# schematic.net
KiCad netlist of a schematic drawn in Altium Designer
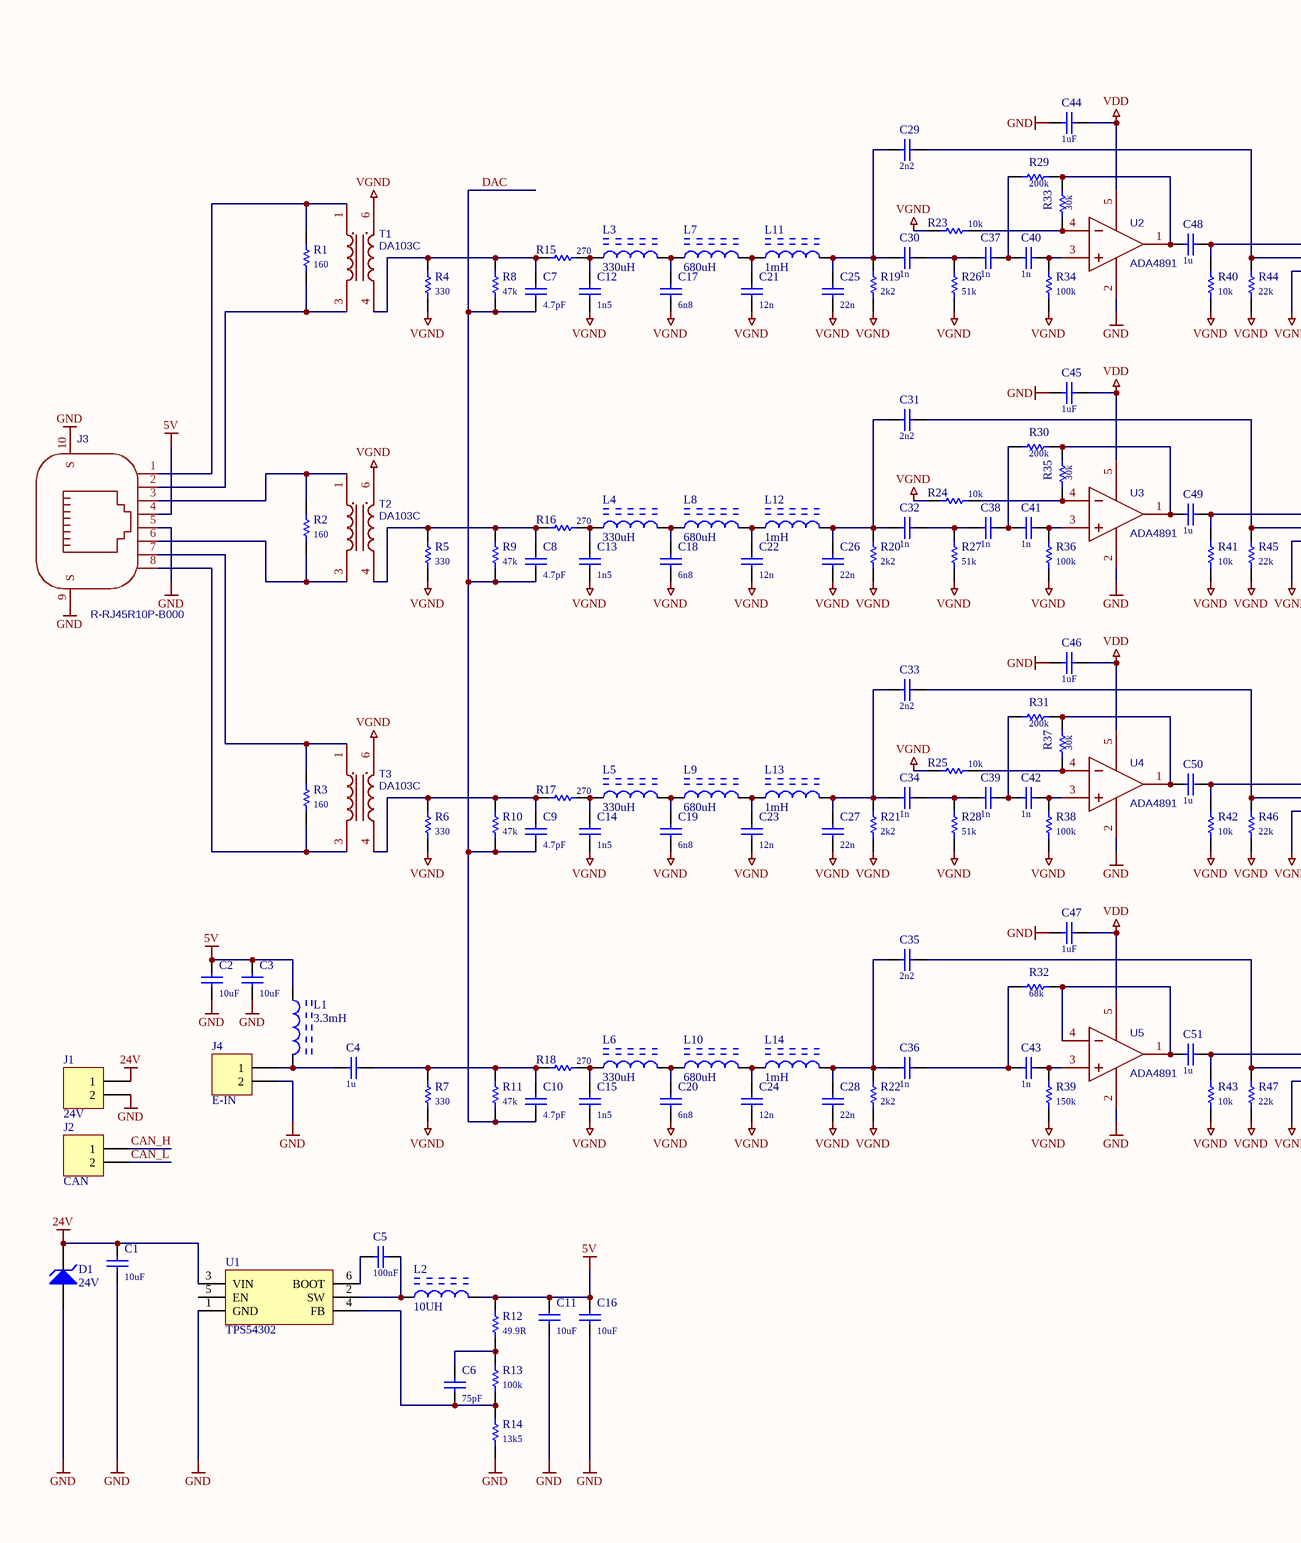
[diagram p0: schematic.SchDoc, left]
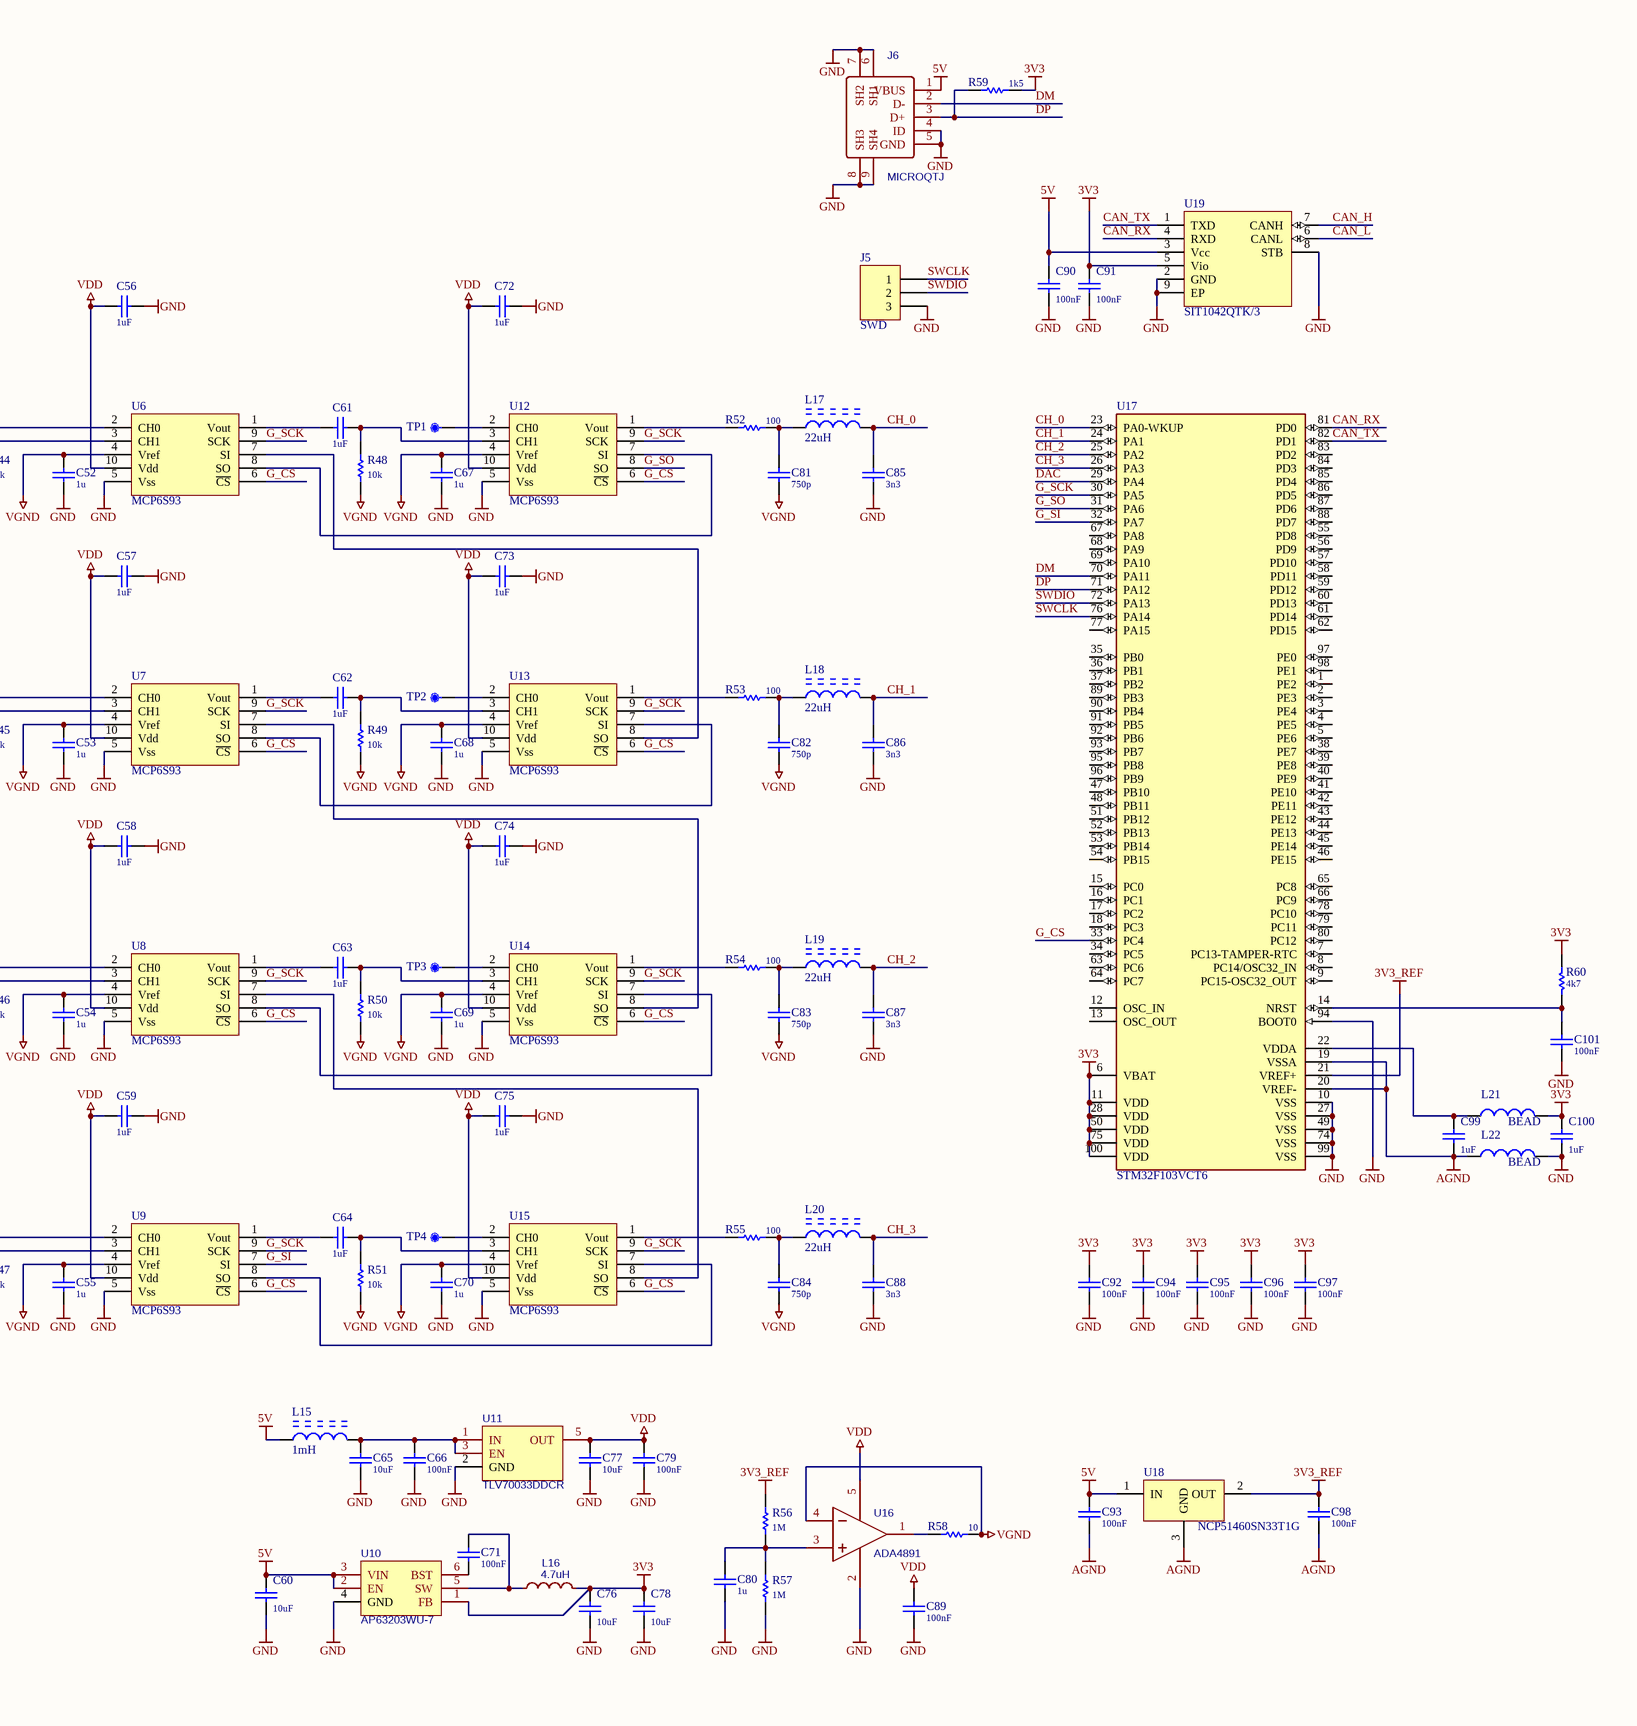
[diagram p1: schematic.SchDoc, right]

(export (version "E")
  (design (tool "Eeschema 10.0.6"))
  (components
    (comp (ref "C1")
      (value "10uF")
      (footprint "C1206")
      (description "10uf 50V 1206")
      (libsource (lib "Miscellaneous Devices") (part "CAP"))
    )
    (comp (ref "C2")
      (value "10uF")
      (footprint "C1206")
      (description "10uf 50V 1206")
      (libsource (lib "Miscellaneous Devices") (part "CAP"))
    )
    (comp (ref "C3")
      (value "10uF")
      (footprint "C1206")
      (description "10uf 50V 1206")
      (libsource (lib "Miscellaneous Devices") (part "CAP"))
    )
    (comp (ref "C4")
      (value "1u")
      (footprint "C0603")
      (description "1u 0603")
      (libsource (lib "Miscellaneous Devices") (part "CAP"))
    )
    (comp (ref "C5")
      (value "100nF")
      (footprint "C0603")
      (description "100nF 0603")
      (libsource (lib "Miscellaneous Devices") (part "CAP"))
    )
    (comp (ref "C6")
      (value "75pF")
      (footprint "C0603")
      (description "75pF 0603")
      (libsource (lib "Miscellaneous Devices") (part "CAP"))
    )
    (comp (ref "C7")
      (value "4.7pF")
      (footprint "C0603")
      (description "4.7pF 0603")
      (libsource (lib "Miscellaneous Devices") (part "CAP"))
    )
    (comp (ref "C8")
      (value "4.7pF")
      (footprint "C0603")
      (description "4.7pF 0603")
      (libsource (lib "Miscellaneous Devices") (part "CAP"))
    )
    (comp (ref "C9")
      (value "4.7pF")
      (footprint "C0603")
      (description "4.7pF 0603")
      (libsource (lib "Miscellaneous Devices") (part "CAP"))
    )
    (comp (ref "C10")
      (value "4.7pF")
      (footprint "C0603")
      (description "4.7pF 0603")
      (libsource (lib "Miscellaneous Devices") (part "CAP"))
    )
    (comp (ref "C11")
      (value "10uF")
      (footprint "C1206")
      (description "10uf 50V 1206")
      (libsource (lib "Miscellaneous Devices") (part "CAP"))
    )
    (comp (ref "C12")
      (value "1n5")
      (footprint "C0603")
      (description "1n5 0603")
      (libsource (lib "Miscellaneous Devices") (part "CAP"))
    )
    (comp (ref "C13")
      (value "1n5")
      (footprint "C0603")
      (description "1n5 0603")
      (libsource (lib "Miscellaneous Devices") (part "CAP"))
    )
    (comp (ref "C14")
      (value "1n5")
      (footprint "C0603")
      (description "1n5 0603")
      (libsource (lib "Miscellaneous Devices") (part "CAP"))
    )
    (comp (ref "C15")
      (value "1n5")
      (footprint "C0603")
      (description "1n5 0603")
      (libsource (lib "Miscellaneous Devices") (part "CAP"))
    )
    (comp (ref "C16")
      (value "10uF")
      (footprint "C1206")
      (description "10uf 50V 1206")
      (libsource (lib "Miscellaneous Devices") (part "CAP"))
    )
    (comp (ref "C17")
      (value "6n8")
      (footprint "C0603")
      (description "6n8 0603")
      (libsource (lib "Miscellaneous Devices") (part "CAP"))
    )
    (comp (ref "C18")
      (value "6n8")
      (footprint "C0603")
      (description "6n8 0603")
      (libsource (lib "Miscellaneous Devices") (part "CAP"))
    )
    (comp (ref "C19")
      (value "6n8")
      (footprint "C0603")
      (description "6n8 0603")
      (libsource (lib "Miscellaneous Devices") (part "CAP"))
    )
    (comp (ref "C20")
      (value "6n8")
      (footprint "C0603")
      (description "6n8 0603")
      (libsource (lib "Miscellaneous Devices") (part "CAP"))
    )
    (comp (ref "C21")
      (value "12n")
      (footprint "C0603")
      (description "12nF 0603")
      (libsource (lib "Miscellaneous Devices") (part "CAP"))
    )
    (comp (ref "C22")
      (value "12n")
      (footprint "C0603")
      (description "12nF 0603")
      (libsource (lib "Miscellaneous Devices") (part "CAP"))
    )
    (comp (ref "C23")
      (value "12n")
      (footprint "C0603")
      (description "12nF 0603")
      (libsource (lib "Miscellaneous Devices") (part "CAP"))
    )
    (comp (ref "C24")
      (value "12n")
      (footprint "C0603")
      (description "12nF 0603")
      (libsource (lib "Miscellaneous Devices") (part "CAP"))
    )
    (comp (ref "C25")
      (value "22n")
      (footprint "C0603")
      (description "22nF 0603")
      (libsource (lib "Miscellaneous Devices") (part "CAP"))
    )
    (comp (ref "C26")
      (value "22n")
      (footprint "C0603")
      (description "22nF 0603")
      (libsource (lib "Miscellaneous Devices") (part "CAP"))
    )
    (comp (ref "C27")
      (value "22n")
      (footprint "C0603")
      (description "22nF 0603")
      (libsource (lib "Miscellaneous Devices") (part "CAP"))
    )
    (comp (ref "C28")
      (value "22n")
      (footprint "C0603")
      (description "22nF 0603")
      (libsource (lib "Miscellaneous Devices") (part "CAP"))
    )
    (comp (ref "C29")
      (value "2n2")
      (footprint "C0603")
      (description "2n2 0603")
      (libsource (lib "Miscellaneous Devices") (part "CAP"))
    )
    (comp (ref "C30")
      (value "1n")
      (footprint "C0603")
      (description "1n 0603")
      (libsource (lib "Miscellaneous Devices") (part "CAP"))
    )
    (comp (ref "C31")
      (value "2n2")
      (footprint "C0603")
      (description "2n2 0603")
      (libsource (lib "Miscellaneous Devices") (part "CAP"))
    )
    (comp (ref "C32")
      (value "1n")
      (footprint "C0603")
      (description "1n 0603")
      (libsource (lib "Miscellaneous Devices") (part "CAP"))
    )
    (comp (ref "C33")
      (value "2n2")
      (footprint "C0603")
      (description "2n2 0603")
      (libsource (lib "Miscellaneous Devices") (part "CAP"))
    )
    (comp (ref "C34")
      (value "1n")
      (footprint "C0603")
      (description "1n 0603")
      (libsource (lib "Miscellaneous Devices") (part "CAP"))
    )
    (comp (ref "C35")
      (value "2n2")
      (footprint "C0603")
      (description "2n2 0603")
      (libsource (lib "Miscellaneous Devices") (part "CAP"))
    )
    (comp (ref "C36")
      (value "1n")
      (footprint "C0603")
      (description "1n 0603")
      (libsource (lib "Miscellaneous Devices") (part "CAP"))
    )
    (comp (ref "C37")
      (value "1n")
      (footprint "C0603")
      (description "1n 0603")
      (libsource (lib "Miscellaneous Devices") (part "CAP"))
    )
    (comp (ref "C38")
      (value "1n")
      (footprint "C0603")
      (description "1n 0603")
      (libsource (lib "Miscellaneous Devices") (part "CAP"))
    )
    (comp (ref "C39")
      (value "1n")
      (footprint "C0603")
      (description "1n 0603")
      (libsource (lib "Miscellaneous Devices") (part "CAP"))
    )
    (comp (ref "C40")
      (value "1n")
      (footprint "C0603")
      (description "1n 0603")
      (libsource (lib "Miscellaneous Devices") (part "CAP"))
    )
    (comp (ref "C41")
      (value "1n")
      (footprint "C0603")
      (description "1n 0603")
      (libsource (lib "Miscellaneous Devices") (part "CAP"))
    )
    (comp (ref "C42")
      (value "1n")
      (footprint "C0603")
      (description "1n 0603")
      (libsource (lib "Miscellaneous Devices") (part "CAP"))
    )
    (comp (ref "C43")
      (value "1n")
      (footprint "C0603")
      (description "1n 0603")
      (libsource (lib "Miscellaneous Devices") (part "CAP"))
    )
    (comp (ref "C44")
      (value "1uF")
      (footprint "C0603")
      (description "1u 0603")
      (libsource (lib "Miscellaneous Devices") (part "CAP"))
    )
    (comp (ref "C45")
      (value "1uF")
      (footprint "C0603")
      (description "1u 0603")
      (libsource (lib "Miscellaneous Devices") (part "CAP"))
    )
    (comp (ref "C46")
      (value "1uF")
      (footprint "C0603")
      (description "1u 0603")
      (libsource (lib "Miscellaneous Devices") (part "CAP"))
    )
    (comp (ref "C47")
      (value "1uF")
      (footprint "C0603")
      (description "1u 0603")
      (libsource (lib "Miscellaneous Devices") (part "CAP"))
    )
    (comp (ref "C48")
      (value "1u")
      (footprint "C0603")
      (description "1u 0603")
      (libsource (lib "Miscellaneous Devices") (part "CAP"))
    )
    (comp (ref "C49")
      (value "1u")
      (footprint "C0603")
      (description "1u 0603")
      (libsource (lib "Miscellaneous Devices") (part "CAP"))
    )
    (comp (ref "C50")
      (value "1u")
      (footprint "C0603")
      (description "1u 0603")
      (libsource (lib "Miscellaneous Devices") (part "CAP"))
    )
    (comp (ref "C51")
      (value "1u")
      (footprint "C0603")
      (description "1u 0603")
      (libsource (lib "Miscellaneous Devices") (part "CAP"))
    )
    (comp (ref "C52")
      (value "1u")
      (footprint "C0603")
      (description "1u 0603")
      (libsource (lib "Miscellaneous Devices") (part "CAP"))
    )
    (comp (ref "C53")
      (value "1u")
      (footprint "C0603")
      (description "1u 0603")
      (libsource (lib "Miscellaneous Devices") (part "CAP"))
    )
    (comp (ref "C54")
      (value "1u")
      (footprint "C0603")
      (description "1u 0603")
      (libsource (lib "Miscellaneous Devices") (part "CAP"))
    )
    (comp (ref "C55")
      (value "1u")
      (footprint "C0603")
      (description "1u 0603")
      (libsource (lib "Miscellaneous Devices") (part "CAP"))
    )
    (comp (ref "C56")
      (value "1uF")
      (footprint "C0603")
      (description "1u 0603")
      (libsource (lib "Miscellaneous Devices") (part "CAP"))
    )
    (comp (ref "C57")
      (value "1uF")
      (footprint "C0603")
      (description "1u 0603")
      (libsource (lib "Miscellaneous Devices") (part "CAP"))
    )
    (comp (ref "C58")
      (value "1uF")
      (footprint "C0603")
      (description "1u 0603")
      (libsource (lib "Miscellaneous Devices") (part "CAP"))
    )
    (comp (ref "C59")
      (value "1uF")
      (footprint "C0603")
      (description "1u 0603")
      (libsource (lib "Miscellaneous Devices") (part "CAP"))
    )
    (comp (ref "C60")
      (value "10uF")
      (footprint "C1206")
      (description "10uf 50V 1206")
      (libsource (lib "Miscellaneous Devices") (part "CAP"))
    )
    (comp (ref "C61")
      (value "1uF")
      (footprint "C0603")
      (description "1u 0603")
      (libsource (lib "Miscellaneous Devices") (part "CAP"))
    )
    (comp (ref "C62")
      (value "1uF")
      (footprint "C0603")
      (description "1u 0603")
      (libsource (lib "Miscellaneous Devices") (part "CAP"))
    )
    (comp (ref "C63")
      (value "1uF")
      (footprint "C0603")
      (description "1u 0603")
      (libsource (lib "Miscellaneous Devices") (part "CAP"))
    )
    (comp (ref "C64")
      (value "1uF")
      (footprint "C0603")
      (description "1u 0603")
      (libsource (lib "Miscellaneous Devices") (part "CAP"))
    )
    (comp (ref "C65")
      (value "10uF")
      (footprint "C0805")
      (description "10uf 50V 1206")
      (libsource (lib "Miscellaneous Devices") (part "CAP"))
    )
    (comp (ref "C66")
      (value "100nF")
      (footprint "C0603")
      (description "100nF 0603")
      (libsource (lib "Miscellaneous Devices") (part "CAP"))
    )
    (comp (ref "C67")
      (value "1u")
      (footprint "C0603")
      (description "1u 0603")
      (libsource (lib "Miscellaneous Devices") (part "CAP"))
    )
    (comp (ref "C68")
      (value "1u")
      (footprint "C0603")
      (description "1u 0603")
      (libsource (lib "Miscellaneous Devices") (part "CAP"))
    )
    (comp (ref "C69")
      (value "1u")
      (footprint "C0603")
      (description "1u 0603")
      (libsource (lib "Miscellaneous Devices") (part "CAP"))
    )
    (comp (ref "C70")
      (value "1u")
      (footprint "C0603")
      (description "1u 0603")
      (libsource (lib "Miscellaneous Devices") (part "CAP"))
    )
    (comp (ref "C71")
      (value "100nF")
      (footprint "C0402")
      (description "100nF 0402")
      (libsource (lib "Miscellaneous Devices") (part "CAP"))
    )
    (comp (ref "C72")
      (value "1uF")
      (footprint "C0603")
      (description "1u 0603")
      (libsource (lib "Miscellaneous Devices") (part "CAP"))
    )
    (comp (ref "C73")
      (value "1uF")
      (footprint "C0603")
      (description "1u 0603")
      (libsource (lib "Miscellaneous Devices") (part "CAP"))
    )
    (comp (ref "C74")
      (value "1uF")
      (footprint "C0603")
      (description "1u 0603")
      (libsource (lib "Miscellaneous Devices") (part "CAP"))
    )
    (comp (ref "C75")
      (value "1uF")
      (footprint "C0603")
      (description "1u 0603")
      (libsource (lib "Miscellaneous Devices") (part "CAP"))
    )
    (comp (ref "C76")
      (value "10uF")
      (footprint "C1206")
      (description "10uf 50V 1206")
      (libsource (lib "Miscellaneous Devices") (part "CAP"))
    )
    (comp (ref "C77")
      (value "10uF")
      (footprint "C0805")
      (description "10uf 50V 1206")
      (libsource (lib "Miscellaneous Devices") (part "CAP"))
    )
    (comp (ref "C78")
      (value "10uF")
      (footprint "C1206")
      (description "10uf 50V 1206")
      (libsource (lib "Miscellaneous Devices") (part "CAP"))
    )
    (comp (ref "C79")
      (value "100nF")
      (footprint "C0603")
      (description "100nF 0603")
      (libsource (lib "Miscellaneous Devices") (part "CAP"))
    )
    (comp (ref "C80")
      (value "1u")
      (footprint "C0603")
      (description "1u 0603")
      (libsource (lib "Miscellaneous Devices") (part "CAP"))
    )
    (comp (ref "C81")
      (value "750p")
      (footprint "C0603")
      (description "750pF 0603")
      (libsource (lib "Miscellaneous Devices") (part "CAP"))
    )
    (comp (ref "C82")
      (value "750p")
      (footprint "C0603")
      (description "750pF 0603")
      (libsource (lib "Miscellaneous Devices") (part "CAP"))
    )
    (comp (ref "C83")
      (value "750p")
      (footprint "C0603")
      (description "750pF 0603")
      (libsource (lib "Miscellaneous Devices") (part "CAP"))
    )
    (comp (ref "C84")
      (value "750p")
      (footprint "C0603")
      (description "750pF 0603")
      (libsource (lib "Miscellaneous Devices") (part "CAP"))
    )
    (comp (ref "C85")
      (value "3n3")
      (footprint "C0603")
      (description "3n3 0603")
      (libsource (lib "Miscellaneous Devices") (part "CAP"))
    )
    (comp (ref "C86")
      (value "3n3")
      (footprint "C0603")
      (description "3n3 0603")
      (libsource (lib "Miscellaneous Devices") (part "CAP"))
    )
    (comp (ref "C87")
      (value "3n3")
      (footprint "C0603")
      (description "3n3 0603")
      (libsource (lib "Miscellaneous Devices") (part "CAP"))
    )
    (comp (ref "C88")
      (value "3n3")
      (footprint "C0603")
      (description "3n3 0603")
      (libsource (lib "Miscellaneous Devices") (part "CAP"))
    )
    (comp (ref "C89")
      (value "100nF")
      (footprint "C0603")
      (description "100nF 0603")
      (libsource (lib "Miscellaneous Devices") (part "CAP"))
    )
    (comp (ref "C90")
      (value "100nF")
      (footprint "C0402")
      (description "100nF 0402")
      (libsource (lib "Miscellaneous Devices") (part "CAP"))
    )
    (comp (ref "C91")
      (value "100nF")
      (footprint "C0402")
      (description "100nF 0402")
      (libsource (lib "Miscellaneous Devices") (part "CAP"))
    )
    (comp (ref "C92")
      (value "100nF")
      (footprint "C0402")
      (description "100nF 0402")
      (libsource (lib "Miscellaneous Devices") (part "CAP"))
    )
    (comp (ref "C93")
      (value "100nF")
      (footprint "C0603")
      (description "100nF 0603")
      (libsource (lib "Miscellaneous Devices") (part "CAP"))
    )
    (comp (ref "C94")
      (value "100nF")
      (footprint "C0402")
      (description "100nF 0402")
      (libsource (lib "Miscellaneous Devices") (part "CAP"))
    )
    (comp (ref "C95")
      (value "100nF")
      (footprint "C0402")
      (description "100nF 0402")
      (libsource (lib "Miscellaneous Devices") (part "CAP"))
    )
    (comp (ref "C96")
      (value "100nF")
      (footprint "C0402")
      (description "100nF 0402")
      (libsource (lib "Miscellaneous Devices") (part "CAP"))
    )
    (comp (ref "C97")
      (value "100nF")
      (footprint "C0402")
      (description "100nF 0402")
      (libsource (lib "Miscellaneous Devices") (part "CAP"))
    )
    (comp (ref "C98")
      (value "100nF")
      (footprint "C0603")
      (description "100nF 0603")
      (libsource (lib "Miscellaneous Devices") (part "CAP"))
    )
    (comp (ref "C99")
      (value "1uF")
      (footprint "C0603")
      (description "1u 0603")
      (libsource (lib "Miscellaneous Devices") (part "CAP"))
    )
    (comp (ref "C100")
      (value "1uF")
      (footprint "C0603")
      (description "1u 0603")
      (libsource (lib "Miscellaneous Devices") (part "CAP"))
    )
    (comp (ref "C101")
      (value "100nF")
      (footprint "C0402")
      (description "100nF 0402")
      (libsource (lib "Miscellaneous Devices") (part "CAP"))
    )
    (comp (ref "D1")
      (value "24V")
      (footprint "SMB")
      (description "P6SMB24A")
      (libsource (lib "Miscellaneous Devices") (part "SMCJ54A"))
    )
    (comp (ref "J1")
      (value "24V")
      (footprint "CONN_DG308-2.54-2P")
      (description "DG308-2.54-02P-14-00A(H)")
      (libsource (lib "Miscellaneous Devices") (part "CONN MOLEX HDR-M 1x4"))
    )
    (comp (ref "J2")
      (value "CAN")
      (footprint "CONN_DG308-2.54-2P")
      (description "DG308-2.54-02P-14-00A(H)")
      (libsource (lib "Miscellaneous Devices") (part "CONN MOLEX HDR-M 1x4"))
    )
    (comp (ref "J3")
      (value "R-RJ45R10P-B000")
      (footprint "RJ45-TH_R-RJ45R10P-B000")
      (libsource (lib "altium-import") (part "root_3_mirrored_R-RJ45R10P-B000_"))
    )
    (comp (ref "J4")
      (value "E-IN")
      (footprint "CONN_F_TYPE")
      (libsource (lib "Miscellaneous Devices") (part "CONN MOLEX HDR-M 1x4"))
    )
    (comp (ref "J5")
      (value "SWD")
      (footprint "HDR-1X3")
      (libsource (lib "Miscellaneous Devices") (part "Header 3"))
    )
    (comp (ref "J6")
      (value "MICROQTJ")
      (footprint "MICRO-USB-SMD_MICROQTJ")
      (description "MicroQTJ")
      (libsource (lib "altium-import") (part "root_0_MICROQTJ_"))
    )
    (comp (ref "L1")
      (value "3.3mH")
      (footprint "IND-TH_BD5.0-L10.5-P14.50-D0.6")
      (description "CKL0510*3.3mH/K-A T")
      (libsource (lib "Miscellaneous Devices") (part "SRN3015-4R7M"))
    )
    (comp (ref "L2")
      (value "10UH")
      (footprint "IND-SMD_L7.2-W6.6_GPSR07X0")
      (description "CYA0630-10UH")
      (libsource (lib "Miscellaneous Devices") (part "SRN3015-100M"))
    )
    (comp (ref "L3")
      (value "330uH")
      (footprint "L1210")
      (description "NLCV32T-331K-PF")
      (libsource (lib "Miscellaneous Devices") (part "SRN3015-4R7M"))
    )
    (comp (ref "L4")
      (value "330uH")
      (footprint "L1210")
      (description "NLCV32T-331K-PF")
      (libsource (lib "Miscellaneous Devices") (part "SRN3015-4R7M"))
    )
    (comp (ref "L5")
      (value "330uH")
      (footprint "L1210")
      (description "NLCV32T-331K-PF")
      (libsource (lib "Miscellaneous Devices") (part "SRN3015-4R7M"))
    )
    (comp (ref "L6")
      (value "330uH")
      (footprint "L1210")
      (description "NLCV32T-331K-PF")
      (libsource (lib "Miscellaneous Devices") (part "SRN3015-4R7M"))
    )
    (comp (ref "L7")
      (value "680uH")
      (footprint "L1210")
      (description "LQH32CN561K23L")
      (libsource (lib "Miscellaneous Devices") (part "SRN3015-4R7M"))
    )
    (comp (ref "L8")
      (value "680uH")
      (footprint "L1210")
      (description "LQH32CN561K23L")
      (libsource (lib "Miscellaneous Devices") (part "SRN3015-4R7M"))
    )
    (comp (ref "L9")
      (value "680uH")
      (footprint "L1210")
      (description "LQH32CN561K23L")
      (libsource (lib "Miscellaneous Devices") (part "SRN3015-4R7M"))
    )
    (comp (ref "L10")
      (value "680uH")
      (footprint "L1210")
      (description "LQH32CN561K23L")
      (libsource (lib "Miscellaneous Devices") (part "SRN3015-4R7M"))
    )
    (comp (ref "L11")
      (value "1mH")
      (footprint "L1210")
      (description "NLFV32T-102K-EF")
      (libsource (lib "Miscellaneous Devices") (part "SRN3015-4R7M"))
    )
    (comp (ref "L12")
      (value "1mH")
      (footprint "L1210")
      (description "NLFV32T-102K-EF")
      (libsource (lib "Miscellaneous Devices") (part "SRN3015-4R7M"))
    )
    (comp (ref "L13")
      (value "1mH")
      (footprint "L1210")
      (description "NLFV32T-102K-EF")
      (libsource (lib "Miscellaneous Devices") (part "SRN3015-4R7M"))
    )
    (comp (ref "L14")
      (value "1mH")
      (footprint "L1210")
      (description "NLFV32T-102K-EF")
      (libsource (lib "Miscellaneous Devices") (part "SRN3015-4R7M"))
    )
    (comp (ref "L15")
      (value "1mH")
      (footprint "L1210")
      (description "NLFV32T-102K-EF")
      (libsource (lib "Miscellaneous Devices") (part "SRN3015-4R7M"))
    )
    (comp (ref "L16")
      (value "4.7uH")
      (footprint "IND-SMD_L4.4-W4.2")
      (description "FXL0420-4R7-M")
      (libsource (lib "altium-import") (part "root_0_4.7uH_"))
    )
    (comp (ref "L17")
      (value "22uH")
      (footprint "L1210")
      (description "NLCV32T-220K-PF")
      (libsource (lib "Miscellaneous Devices") (part "SRN3015-4R7M"))
    )
    (comp (ref "L18")
      (value "22uH")
      (footprint "L1210")
      (description "NLCV32T-220K-PF")
      (libsource (lib "Miscellaneous Devices") (part "SRN3015-4R7M"))
    )
    (comp (ref "L19")
      (value "22uH")
      (footprint "L1210")
      (description "NLCV32T-220K-PF")
      (libsource (lib "Miscellaneous Devices") (part "SRN3015-4R7M"))
    )
    (comp (ref "L20")
      (value "22uH")
      (footprint "L1210")
      (description "NLCV32T-220K-PF")
      (libsource (lib "Miscellaneous Devices") (part "SRN3015-4R7M"))
    )
    (comp (ref "L21")
      (value "BEAD")
      (footprint "L0402")
      (description "BEAD 0402")
      (libsource (lib "Miscellaneous Devices") (part "BLM18AG601SN1D"))
    )
    (comp (ref "L22")
      (value "BEAD")
      (footprint "L0402")
      (description "BEAD 0402")
      (libsource (lib "Miscellaneous Devices") (part "BLM18AG601SN1D"))
    )
    (comp (ref "R1")
      (value "160")
      (footprint "R0603")
      (description "160R 0603")
      (libsource (lib "Miscellaneous Devices") (part "RES"))
    )
    (comp (ref "R2")
      (value "160")
      (footprint "R0603")
      (description "160R 0603")
      (libsource (lib "Miscellaneous Devices") (part "RES"))
    )
    (comp (ref "R3")
      (value "160")
      (footprint "R0603")
      (description "160R 0603")
      (libsource (lib "Miscellaneous Devices") (part "RES"))
    )
    (comp (ref "R4")
      (value "330")
      (footprint "R0603")
      (description "330R 0603")
      (libsource (lib "Miscellaneous Devices") (part "RES"))
    )
    (comp (ref "R5")
      (value "330")
      (footprint "R0603")
      (description "330R 0603")
      (libsource (lib "Miscellaneous Devices") (part "RES"))
    )
    (comp (ref "R6")
      (value "330")
      (footprint "R0603")
      (description "330R 0603")
      (libsource (lib "Miscellaneous Devices") (part "RES"))
    )
    (comp (ref "R7")
      (value "330")
      (footprint "R0603")
      (description "330R 0603")
      (libsource (lib "Miscellaneous Devices") (part "RES"))
    )
    (comp (ref "R8")
      (value "47k")
      (footprint "R0603")
      (description "47k 0603")
      (libsource (lib "Miscellaneous Devices") (part "RES"))
    )
    (comp (ref "R9")
      (value "47k")
      (footprint "R0603")
      (description "47k 0603")
      (libsource (lib "Miscellaneous Devices") (part "RES"))
    )
    (comp (ref "R10")
      (value "47k")
      (footprint "R0603")
      (description "47k 0603")
      (libsource (lib "Miscellaneous Devices") (part "RES"))
    )
    (comp (ref "R11")
      (value "47k")
      (footprint "R0603")
      (description "47k 0603")
      (libsource (lib "Miscellaneous Devices") (part "RES"))
    )
    (comp (ref "R12")
      (value "49.9R")
      (footprint "R0603")
      (description "49R9 0603")
      (libsource (lib "Miscellaneous Devices") (part "RES"))
    )
    (comp (ref "R13")
      (value "100k")
      (footprint "R0603")
      (description "100k 0603")
      (libsource (lib "") (part "RES_1"))
    )
    (comp (ref "R14")
      (value "13k5")
      (footprint "R0603")
      (description "13k7 0603")
      (libsource (lib "") (part "RES_1"))
    )
    (comp (ref "R15")
      (value "270")
      (footprint "R0603")
      (description "270R 0603")
      (libsource (lib "Miscellaneous Devices") (part "RES"))
    )
    (comp (ref "R16")
      (value "270")
      (footprint "R0603")
      (description "270R 0603")
      (libsource (lib "Miscellaneous Devices") (part "RES"))
    )
    (comp (ref "R17")
      (value "270")
      (footprint "R0603")
      (description "270R 0603")
      (libsource (lib "Miscellaneous Devices") (part "RES"))
    )
    (comp (ref "R18")
      (value "270")
      (footprint "R0603")
      (description "270R 0603")
      (libsource (lib "Miscellaneous Devices") (part "RES"))
    )
    (comp (ref "R19")
      (value "2k2")
      (footprint "R0603")
      (description "2k2 0603")
      (libsource (lib "Miscellaneous Devices") (part "RES"))
    )
    (comp (ref "R20")
      (value "2k2")
      (footprint "R0603")
      (description "2k2 0603")
      (libsource (lib "Miscellaneous Devices") (part "RES"))
    )
    (comp (ref "R21")
      (value "2k2")
      (footprint "R0603")
      (description "2k2 0603")
      (libsource (lib "Miscellaneous Devices") (part "RES"))
    )
    (comp (ref "R22")
      (value "2k2")
      (footprint "R0603")
      (description "2k2 0603")
      (libsource (lib "Miscellaneous Devices") (part "RES"))
    )
    (comp (ref "R23")
      (value "10k")
      (footprint "R0603")
      (description "10k 0603")
      (libsource (lib "Miscellaneous Devices") (part "RES"))
    )
    (comp (ref "R24")
      (value "10k")
      (footprint "R0603")
      (description "10k 0603")
      (libsource (lib "Miscellaneous Devices") (part "RES"))
    )
    (comp (ref "R25")
      (value "10k")
      (footprint "R0603")
      (description "10k 0603")
      (libsource (lib "Miscellaneous Devices") (part "RES"))
    )
    (comp (ref "R26")
      (value "51k")
      (footprint "R0603")
      (description "51k 0603")
      (libsource (lib "Miscellaneous Devices") (part "RES"))
    )
    (comp (ref "R27")
      (value "51k")
      (footprint "R0603")
      (description "51k 0603")
      (libsource (lib "Miscellaneous Devices") (part "RES"))
    )
    (comp (ref "R28")
      (value "51k")
      (footprint "R0603")
      (description "51k 0603")
      (libsource (lib "Miscellaneous Devices") (part "RES"))
    )
    (comp (ref "R29")
      (value "200k")
      (footprint "R0603")
      (description "200k 0603")
      (libsource (lib "Miscellaneous Devices") (part "RES"))
    )
    (comp (ref "R30")
      (value "200k")
      (footprint "R0603")
      (description "200k 0603")
      (libsource (lib "Miscellaneous Devices") (part "RES"))
    )
    (comp (ref "R31")
      (value "200k")
      (footprint "R0603")
      (description "200k 0603")
      (libsource (lib "Miscellaneous Devices") (part "RES"))
    )
    (comp (ref "R32")
      (value "68k")
      (footprint "R0603")
      (description "68k 0603")
      (libsource (lib "Miscellaneous Devices") (part "RES"))
    )
    (comp (ref "R33")
      (value "30k")
      (footprint "R0603")
      (description "30k 0603")
      (libsource (lib "Miscellaneous Devices") (part "RES"))
    )
    (comp (ref "R34")
      (value "100k")
      (footprint "R0603")
      (description "100k 0603")
      (libsource (lib "Miscellaneous Devices") (part "RES"))
    )
    (comp (ref "R35")
      (value "30k")
      (footprint "R0603")
      (description "30k 0603")
      (libsource (lib "Miscellaneous Devices") (part "RES"))
    )
    (comp (ref "R36")
      (value "100k")
      (footprint "R0603")
      (description "100k 0603")
      (libsource (lib "Miscellaneous Devices") (part "RES"))
    )
    (comp (ref "R37")
      (value "30k")
      (footprint "R0603")
      (description "30k 0603")
      (libsource (lib "Miscellaneous Devices") (part "RES"))
    )
    (comp (ref "R38")
      (value "100k")
      (footprint "R0603")
      (description "100k 0603")
      (libsource (lib "Miscellaneous Devices") (part "RES"))
    )
    (comp (ref "R39")
      (value "150k")
      (footprint "R0603")
      (description "150k 0603")
      (libsource (lib "Miscellaneous Devices") (part "RES"))
    )
    (comp (ref "R40")
      (value "10k")
      (footprint "R0603")
      (description "10k 0603")
      (libsource (lib "Miscellaneous Devices") (part "RES"))
    )
    (comp (ref "R41")
      (value "10k")
      (footprint "R0603")
      (description "10k 0603")
      (libsource (lib "Miscellaneous Devices") (part "RES"))
    )
    (comp (ref "R42")
      (value "10k")
      (footprint "R0603")
      (description "10k 0603")
      (libsource (lib "Miscellaneous Devices") (part "RES"))
    )
    (comp (ref "R43")
      (value "10k")
      (footprint "R0603")
      (description "10k 0603")
      (libsource (lib "Miscellaneous Devices") (part "RES"))
    )
    (comp (ref "R44")
      (value "22k")
      (footprint "R0603")
      (description "22k 0603")
      (libsource (lib "Miscellaneous Devices") (part "RES"))
    )
    (comp (ref "R45")
      (value "22k")
      (footprint "R0603")
      (description "22k 0603")
      (libsource (lib "Miscellaneous Devices") (part "RES"))
    )
    (comp (ref "R46")
      (value "22k")
      (footprint "R0603")
      (description "22k 0603")
      (libsource (lib "Miscellaneous Devices") (part "RES"))
    )
    (comp (ref "R47")
      (value "22k")
      (footprint "R0603")
      (description "22k 0603")
      (libsource (lib "Miscellaneous Devices") (part "RES"))
    )
    (comp (ref "R48")
      (value "10k")
      (footprint "R0603")
      (description "10k 0603")
      (libsource (lib "Miscellaneous Devices") (part "RES"))
    )
    (comp (ref "R49")
      (value "10k")
      (footprint "R0603")
      (description "10k 0603")
      (libsource (lib "Miscellaneous Devices") (part "RES"))
    )
    (comp (ref "R50")
      (value "10k")
      (footprint "R0603")
      (description "10k 0603")
      (libsource (lib "Miscellaneous Devices") (part "RES"))
    )
    (comp (ref "R51")
      (value "10k")
      (footprint "R0603")
      (description "10k 0603")
      (libsource (lib "Miscellaneous Devices") (part "RES"))
    )
    (comp (ref "R52")
      (value "100")
      (footprint "R0603")
      (description "100R 0603")
      (libsource (lib "Miscellaneous Devices") (part "RES"))
    )
    (comp (ref "R53")
      (value "100")
      (footprint "R0603")
      (description "100R 0603")
      (libsource (lib "Miscellaneous Devices") (part "RES"))
    )
    (comp (ref "R54")
      (value "100")
      (footprint "R0603")
      (description "100R 0603")
      (libsource (lib "Miscellaneous Devices") (part "RES"))
    )
    (comp (ref "R55")
      (value "100")
      (footprint "R0603")
      (description "100R 0603")
      (libsource (lib "Miscellaneous Devices") (part "RES"))
    )
    (comp (ref "R56")
      (value "1M")
      (footprint "R0603")
      (description "1M 0603")
      (libsource (lib "Miscellaneous Devices") (part "RES"))
    )
    (comp (ref "R57")
      (value "1M")
      (footprint "R0603")
      (description "1M 0603")
      (libsource (lib "Miscellaneous Devices") (part "RES"))
    )
    (comp (ref "R58")
      (value "10")
      (footprint "R0805")
      (description "10R 0805")
      (libsource (lib "Miscellaneous Devices") (part "RES"))
    )
    (comp (ref "R59")
      (value "1k5")
      (footprint "R0402")
      (description "1k5 0402")
      (libsource (lib "Miscellaneous Devices") (part "RES"))
    )
    (comp (ref "R60")
      (value "4k7")
      (footprint "R0402")
      (description "4k7 0402")
      (libsource (lib "") (part "RES_1"))
    )
    (comp (ref "T1")
      (value "DA103C")
      (footprint "TR_DA103C")
      (libsource (lib "altium-import") (part "root_3_mirrored_DLW43SH101XK2L_"))
    )
    (comp (ref "T2")
      (value "DA103C")
      (footprint "TR_DA103C")
      (libsource (lib "altium-import") (part "root_3_mirrored_DLW43SH101XK2L_"))
    )
    (comp (ref "T3")
      (value "DA103C")
      (footprint "TR_DA103C")
      (libsource (lib "altium-import") (part "root_3_mirrored_DLW43SH101XK2L_"))
    )
    (comp (ref "TP1")
      (value "~")
      (footprint "TP_TH_MICRO")
      (libsource (lib "Miscellaneous Devices") (part "TP_Dup1"))
    )
    (comp (ref "TP2")
      (value "~")
      (footprint "TP_TH_MICRO")
      (libsource (lib "Miscellaneous Devices") (part "TP_Dup1"))
    )
    (comp (ref "TP3")
      (value "~")
      (footprint "TP_TH_MICRO")
      (libsource (lib "Miscellaneous Devices") (part "TP_Dup1"))
    )
    (comp (ref "TP4")
      (value "~")
      (footprint "TP_TH_MICRO")
      (libsource (lib "Miscellaneous Devices") (part "TP_Dup1"))
    )
    (comp (ref "U1")
      (value "TPS54302")
      (footprint "SOT-23-6")
      (description "TPS54302DDCR")
      (libsource (lib "Miscellaneous Devices") (part "LM27313XMFX"))
    )
    (comp (ref "U2")
      (value "ADA4891")
      (footprint "SOT-23-5")
      (description "ADA4891-1ARJZ-R7")
      (libsource (lib "altium-import") (part "root_0_ADA4891-1ARJZ-R7_"))
    )
    (comp (ref "U3")
      (value "ADA4891")
      (footprint "SOT-23-5")
      (description "ADA4891-1ARJZ-R7")
      (libsource (lib "altium-import") (part "root_0_ADA4891-1ARJZ-R7_"))
    )
    (comp (ref "U4")
      (value "ADA4891")
      (footprint "SOT-23-5")
      (description "ADA4891-1ARJZ-R7")
      (libsource (lib "altium-import") (part "root_0_ADA4891-1ARJZ-R7_"))
    )
    (comp (ref "U5")
      (value "ADA4891")
      (footprint "SOT-23-5")
      (description "ADA4891-1ARJZ-R7")
      (libsource (lib "altium-import") (part "root_0_ADA4891-1ARJZ-R7_"))
    )
    (comp (ref "U6") (value "MCP6S93") (footprint "MSOP10") (libsource (lib "Schlib1") (part "MCP6S93")))
    (comp (ref "U7") (value "MCP6S93") (footprint "MSOP10") (libsource (lib "Schlib1") (part "MCP6S93")))
    (comp (ref "U8") (value "MCP6S93") (footprint "MSOP10") (libsource (lib "Schlib1") (part "MCP6S93")))
    (comp (ref "U9") (value "MCP6S93") (footprint "MSOP10") (libsource (lib "Schlib1") (part "MCP6S93")))
    (comp (ref "U10")
      (value "AP63203WU-7")
      (footprint "SOT-23-6")
      (libsource (lib "Schlib1") (part "AP63203WU-7"))
    )
    (comp (ref "U11")
      (value "TLV70033DDCR")
      (footprint "SOT-23-5")
      (libsource (lib "Schlib1") (part "TLV70033DDCR"))
    )
    (comp (ref "U12") (value "MCP6S93") (footprint "MSOP10") (libsource (lib "Schlib1") (part "MCP6S93")))
    (comp (ref "U13") (value "MCP6S93") (footprint "MSOP10") (libsource (lib "Schlib1") (part "MCP6S93")))
    (comp (ref "U14") (value "MCP6S93") (footprint "MSOP10") (libsource (lib "Schlib1") (part "MCP6S93")))
    (comp (ref "U15") (value "MCP6S93") (footprint "MSOP10") (libsource (lib "Schlib1") (part "MCP6S93")))
    (comp (ref "U16")
      (value "ADA4891")
      (footprint "SOT-23-5")
      (description "ADA4891-1ARJZ-R7")
      (libsource (lib "altium-import") (part "root_0_ADA4891-1ARJZ-R7_"))
    )
    (comp (ref "U17")
      (value "STM32F103VCT6")
      (footprint "lib_2023:LQFP-100")
      (libsource (lib "SnapEDAsch") (part "STM32F103VCT6"))
    )
    (comp (ref "U18")
      (value "NCP51460SN33T1G")
      (footprint "SOT-23")
      (libsource (lib "Schlib1") (part "NCP51460SN33T1G"))
    )
    (comp (ref "U19")
      (value "SIT1042QTK/3")
      (footprint "DFN8_3X3_P065")
      (libsource (lib "Miscellaneous Devices") (part "LTC2875"))
    )
  )
  (nets
    (net (code "1") (name "/CAN_H") (class "Default")
      (node (ref "J2") (pin "1") (pinfunction "1_1") (pintype "passive"))
      (node (ref "U19") (pin "7") (pinfunction "CANH_7") (pintype "bidirectional"))
    )
    (net (code "2") (name "/CAN_L") (class "Default")
      (node (ref "J2") (pin "2") (pinfunction "2_2") (pintype "passive"))
      (node (ref "U19") (pin "6") (pinfunction "CANL_6") (pintype "bidirectional"))
    )
    (net (code "3") (name "/CAN_RX") (class "Default")
      (node (ref "U17") (pin "81") (pinfunction "PD0_81") (pintype "bidirectional"))
      (node (ref "U19") (pin "4") (pinfunction "RXD_4") (pintype "passive"))
    )
    (net (code "4") (name "/CAN_TX") (class "Default")
      (node (ref "U17") (pin "82") (pinfunction "PD1_82") (pintype "bidirectional"))
      (node (ref "U19") (pin "1") (pinfunction "TXD_1") (pintype "passive"))
    )
    (net (code "5") (name "/CH_0") (class "Default")
      (node (ref "C85") (pin "1") (pinfunction "1_1") (pintype "passive"))
      (node (ref "L17") (pin "2") (pinfunction "2_2") (pintype "passive"))
      (node (ref "U17") (pin "23") (pinfunction "PA0-WKUP_23") (pintype "bidirectional"))
    )
    (net (code "6") (name "/CH_1") (class "Default")
      (node (ref "C86") (pin "1") (pinfunction "1_1") (pintype "passive"))
      (node (ref "L18") (pin "2") (pinfunction "2_2") (pintype "passive"))
      (node (ref "U17") (pin "24") (pinfunction "PA1_24") (pintype "bidirectional"))
    )
    (net (code "7") (name "/CH_2") (class "Default")
      (node (ref "C87") (pin "1") (pinfunction "1_1") (pintype "passive"))
      (node (ref "L19") (pin "2") (pinfunction "2_2") (pintype "passive"))
      (node (ref "U17") (pin "25") (pinfunction "PA2_25") (pintype "bidirectional"))
    )
    (net (code "8") (name "/CH_3") (class "Default")
      (node (ref "C88") (pin "1") (pinfunction "1_1") (pintype "passive"))
      (node (ref "L20") (pin "2") (pinfunction "2_2") (pintype "passive"))
      (node (ref "U17") (pin "26") (pinfunction "PA3_26") (pintype "bidirectional"))
    )
    (net (code "9") (name "/DAC") (class "Default")
      (node (ref "C10") (pin "1") (pinfunction "1_1") (pintype "passive"))
      (node (ref "C7") (pin "1") (pinfunction "1_1") (pintype "passive"))
      (node (ref "C8") (pin "1") (pinfunction "1_1") (pintype "passive"))
      (node (ref "C9") (pin "1") (pinfunction "1_1") (pintype "passive"))
      (node (ref "R10") (pin "1") (pinfunction "1_1") (pintype "passive"))
      (node (ref "R11") (pin "1") (pinfunction "1_1") (pintype "passive"))
      (node (ref "R8") (pin "1") (pinfunction "1_1") (pintype "passive"))
      (node (ref "R9") (pin "1") (pinfunction "1_1") (pintype "passive"))
      (node (ref "U17") (pin "29") (pinfunction "PA4_29") (pintype "bidirectional"))
    )
    (net (code "10") (name "/DM") (class "Default")
      (node (ref "J6") (pin "2") (pinfunction "D-_2") (pintype "passive"))
      (node (ref "U17") (pin "70") (pinfunction "PA11_70") (pintype "bidirectional"))
    )
    (net (code "11") (name "/DP") (class "Default")
      (node (ref "J6") (pin "3") (pinfunction "D+_3") (pintype "passive"))
      (node (ref "R59") (pin "2") (pinfunction "2_2") (pintype "passive"))
      (node (ref "U17") (pin "71") (pinfunction "PA12_71") (pintype "bidirectional"))
    )
    (net (code "12") (name "/G_CS") (class "Default")
      (node (ref "U12") (pin "6") (pinfunction "~{CS}_6") (pintype "passive"))
      (node (ref "U13") (pin "6") (pinfunction "~{CS}_6") (pintype "passive"))
      (node (ref "U14") (pin "6") (pinfunction "~{CS}_6") (pintype "passive"))
      (node (ref "U15") (pin "6") (pinfunction "~{CS}_6") (pintype "passive"))
      (node (ref "U17") (pin "33") (pinfunction "PC4_33") (pintype "bidirectional"))
      (node (ref "U6") (pin "6") (pinfunction "~{CS}_6") (pintype "passive"))
      (node (ref "U7") (pin "6") (pinfunction "~{CS}_6") (pintype "passive"))
      (node (ref "U8") (pin "6") (pinfunction "~{CS}_6") (pintype "passive"))
      (node (ref "U9") (pin "6") (pinfunction "~{CS}_6") (pintype "passive"))
    )
    (net (code "13") (name "/G_SCK") (class "Default")
      (node (ref "U12") (pin "9") (pinfunction "SCK_9") (pintype "passive"))
      (node (ref "U13") (pin "9") (pinfunction "SCK_9") (pintype "passive"))
      (node (ref "U14") (pin "9") (pinfunction "SCK_9") (pintype "passive"))
      (node (ref "U15") (pin "9") (pinfunction "SCK_9") (pintype "passive"))
      (node (ref "U17") (pin "30") (pinfunction "PA5_30") (pintype "bidirectional"))
      (node (ref "U6") (pin "9") (pinfunction "SCK_9") (pintype "passive"))
      (node (ref "U7") (pin "9") (pinfunction "SCK_9") (pintype "passive"))
      (node (ref "U8") (pin "9") (pinfunction "SCK_9") (pintype "passive"))
      (node (ref "U9") (pin "9") (pinfunction "SCK_9") (pintype "passive"))
    )
    (net (code "14") (name "/G_SI") (class "Default")
      (node (ref "U17") (pin "32") (pinfunction "PA7_32") (pintype "bidirectional"))
      (node (ref "U9") (pin "7") (pinfunction "SI_7") (pintype "passive"))
    )
    (net (code "15") (name "/G_SO") (class "Default")
      (node (ref "U12") (pin "8") (pinfunction "SO_8") (pintype "passive"))
      (node (ref "U17") (pin "31") (pinfunction "PA6_31") (pintype "bidirectional"))
    )
    (net (code "16") (name "/SWCLK") (class "Default")
      (node (ref "J5") (pin "1") (pinfunction "1_1") (pintype "passive"))
      (node (ref "U17") (pin "76") (pinfunction "PA14_76") (pintype "bidirectional"))
    )
    (net (code "17") (name "/SWDIO") (class "Default")
      (node (ref "J5") (pin "2") (pinfunction "2_2") (pintype "passive"))
      (node (ref "U17") (pin "72") (pinfunction "PA13_72") (pintype "bidirectional"))
    )
    (net (code "18") (name "3V3") (class "Default")
      (node (ref "C100") (pin "2") (pinfunction "2_2") (pintype "passive"))
      (node (ref "C76") (pin "2") (pinfunction "2_2") (pintype "passive"))
      (node (ref "C78") (pin "2") (pinfunction "2_2") (pintype "passive"))
      (node (ref "C91") (pin "2") (pinfunction "2_2") (pintype "passive"))
      (node (ref "C92") (pin "2") (pinfunction "2_2") (pintype "passive"))
      (node (ref "C94") (pin "2") (pinfunction "2_2") (pintype "passive"))
      (node (ref "C95") (pin "2") (pinfunction "2_2") (pintype "passive"))
      (node (ref "C96") (pin "2") (pinfunction "2_2") (pintype "passive"))
      (node (ref "C97") (pin "2") (pinfunction "2_2") (pintype "passive"))
      (node (ref "L16") (pin "2") (pinfunction "2_2") (pintype "passive"))
      (node (ref "L21") (pin "1") (pinfunction "1_1") (pintype "passive"))
      (node (ref "R59") (pin "1") (pinfunction "1_1") (pintype "passive"))
      (node (ref "R60") (pin "1") (pinfunction "1_1") (pintype "passive"))
      (node (ref "U10") (pin "1") (pinfunction "FB_1") (pintype "passive"))
      (node (ref "U17") (pin "100") (pinfunction "VDD_100") (pintype "power_in"))
      (node (ref "U17") (pin "11") (pinfunction "VDD_11") (pintype "power_in"))
      (node (ref "U17") (pin "28") (pinfunction "VDD_28") (pintype "power_in"))
      (node (ref "U17") (pin "50") (pinfunction "VDD_50") (pintype "power_in"))
      (node (ref "U17") (pin "6") (pinfunction "VBAT_6") (pintype "power_in"))
      (node (ref "U17") (pin "75") (pinfunction "VDD_75") (pintype "power_in"))
      (node (ref "U19") (pin "5") (pinfunction "Vio_5") (pintype "passive"))
    )
    (net (code "19") (name "3V3_REF") (class "Default")
      (node (ref "C98") (pin "2") (pinfunction "2_2") (pintype "passive"))
      (node (ref "R56") (pin "2") (pinfunction "2_2") (pintype "passive"))
      (node (ref "U17") (pin "21") (pinfunction "VREF+_21") (pintype "power_in"))
      (node (ref "U18") (pin "2") (pinfunction "OUT_2") (pintype "passive"))
    )
    (net (code "20") (name "5V") (class "Default")
      (node (ref "C11") (pin "2") (pinfunction "2_2") (pintype "passive"))
      (node (ref "C16") (pin "2") (pinfunction "2_2") (pintype "passive"))
      (node (ref "C2") (pin "2") (pinfunction "2_2") (pintype "passive"))
      (node (ref "C3") (pin "2") (pinfunction "2_2") (pintype "passive"))
      (node (ref "C60") (pin "2") (pinfunction "2_2") (pintype "passive"))
      (node (ref "C90") (pin "2") (pinfunction "2_2") (pintype "passive"))
      (node (ref "C93") (pin "2") (pinfunction "2_2") (pintype "passive"))
      (node (ref "J3") (pin "4") (pinfunction "4_4") (pintype "passive"))
      (node (ref "J6") (pin "1") (pinfunction "VBUS_1") (pintype "passive"))
      (node (ref "L1") (pin "1") (pinfunction "1_1") (pintype "passive"))
      (node (ref "L15") (pin "1") (pinfunction "1_1") (pintype "passive"))
      (node (ref "L2") (pin "2") (pinfunction "2_2") (pintype "passive"))
      (node (ref "R12") (pin "1") (pinfunction "1_1") (pintype "passive"))
      (node (ref "U10") (pin "2") (pinfunction "EN_2") (pintype "passive"))
      (node (ref "U10") (pin "3") (pinfunction "VIN_3") (pintype "passive"))
      (node (ref "U18") (pin "1") (pinfunction "IN_1") (pintype "passive"))
      (node (ref "U19") (pin "3") (pinfunction "Vcc_3") (pintype "passive"))
    )
    (net (code "21") (name "24V") (class "Default")
      (node (ref "C1") (pin "2") (pinfunction "2_2") (pintype "passive"))
      (node (ref "D1") (pin "2") (pinfunction "K_2") (pintype "passive"))
      (node (ref "J1") (pin "1") (pinfunction "1_1") (pintype "passive"))
      (node (ref "U1") (pin "3") (pinfunction "VIN_3") (pintype "passive"))
    )
    (net (code "22") (name "AGND") (class "Default")
      (node (ref "C93") (pin "1") (pinfunction "1_1") (pintype "passive"))
      (node (ref "C98") (pin "1") (pinfunction "1_1") (pintype "passive"))
      (node (ref "C99") (pin "1") (pinfunction "1_1") (pintype "passive"))
      (node (ref "L22") (pin "2") (pinfunction "2_2") (pintype "passive"))
      (node (ref "U17") (pin "19") (pinfunction "VSSA_19") (pintype "power_in"))
      (node (ref "U17") (pin "20") (pinfunction "VREF-_20") (pintype "power_in"))
      (node (ref "U18") (pin "3") (pinfunction "GND_3") (pintype "passive"))
    )
    (net (code "23") (name "GND") (class "Default")
      (node (ref "C1") (pin "1") (pinfunction "1_1") (pintype "passive"))
      (node (ref "C100") (pin "1") (pinfunction "1_1") (pintype "passive"))
      (node (ref "C101") (pin "1") (pinfunction "1_1") (pintype "passive"))
      (node (ref "C11") (pin "1") (pinfunction "1_1") (pintype "passive"))
      (node (ref "C16") (pin "1") (pinfunction "1_1") (pintype "passive"))
      (node (ref "C2") (pin "1") (pinfunction "1_1") (pintype "passive"))
      (node (ref "C3") (pin "1") (pinfunction "1_1") (pintype "passive"))
      (node (ref "C44") (pin "1") (pinfunction "1_1") (pintype "passive"))
      (node (ref "C45") (pin "1") (pinfunction "1_1") (pintype "passive"))
      (node (ref "C46") (pin "1") (pinfunction "1_1") (pintype "passive"))
      (node (ref "C47") (pin "1") (pinfunction "1_1") (pintype "passive"))
      (node (ref "C52") (pin "2") (pinfunction "2_2") (pintype "passive"))
      (node (ref "C53") (pin "2") (pinfunction "2_2") (pintype "passive"))
      (node (ref "C54") (pin "2") (pinfunction "2_2") (pintype "passive"))
      (node (ref "C55") (pin "2") (pinfunction "2_2") (pintype "passive"))
      (node (ref "C56") (pin "1") (pinfunction "1_1") (pintype "passive"))
      (node (ref "C57") (pin "1") (pinfunction "1_1") (pintype "passive"))
      (node (ref "C58") (pin "1") (pinfunction "1_1") (pintype "passive"))
      (node (ref "C59") (pin "1") (pinfunction "1_1") (pintype "passive"))
      (node (ref "C60") (pin "1") (pinfunction "1_1") (pintype "passive"))
      (node (ref "C65") (pin "1") (pinfunction "1_1") (pintype "passive"))
      (node (ref "C66") (pin "1") (pinfunction "1_1") (pintype "passive"))
      (node (ref "C67") (pin "2") (pinfunction "2_2") (pintype "passive"))
      (node (ref "C68") (pin "2") (pinfunction "2_2") (pintype "passive"))
      (node (ref "C69") (pin "2") (pinfunction "2_2") (pintype "passive"))
      (node (ref "C70") (pin "2") (pinfunction "2_2") (pintype "passive"))
      (node (ref "C72") (pin "1") (pinfunction "1_1") (pintype "passive"))
      (node (ref "C73") (pin "1") (pinfunction "1_1") (pintype "passive"))
      (node (ref "C74") (pin "1") (pinfunction "1_1") (pintype "passive"))
      (node (ref "C75") (pin "1") (pinfunction "1_1") (pintype "passive"))
      (node (ref "C76") (pin "1") (pinfunction "1_1") (pintype "passive"))
      (node (ref "C77") (pin "1") (pinfunction "1_1") (pintype "passive"))
      (node (ref "C78") (pin "1") (pinfunction "1_1") (pintype "passive"))
      (node (ref "C79") (pin "1") (pinfunction "1_1") (pintype "passive"))
      (node (ref "C80") (pin "2") (pinfunction "2_2") (pintype "passive"))
      (node (ref "C85") (pin "2") (pinfunction "2_2") (pintype "passive"))
      (node (ref "C86") (pin "2") (pinfunction "2_2") (pintype "passive"))
      (node (ref "C87") (pin "2") (pinfunction "2_2") (pintype "passive"))
      (node (ref "C88") (pin "2") (pinfunction "2_2") (pintype "passive"))
      (node (ref "C89") (pin "1") (pinfunction "1_1") (pintype "passive"))
      (node (ref "C90") (pin "1") (pinfunction "1_1") (pintype "passive"))
      (node (ref "C91") (pin "1") (pinfunction "1_1") (pintype "passive"))
      (node (ref "C92") (pin "1") (pinfunction "1_1") (pintype "passive"))
      (node (ref "C94") (pin "1") (pinfunction "1_1") (pintype "passive"))
      (node (ref "C95") (pin "1") (pinfunction "1_1") (pintype "passive"))
      (node (ref "C96") (pin "1") (pinfunction "1_1") (pintype "passive"))
      (node (ref "C97") (pin "1") (pinfunction "1_1") (pintype "passive"))
      (node (ref "D1") (pin "1") (pinfunction "A_1") (pintype "passive"))
      (node (ref "J1") (pin "2") (pinfunction "2_2") (pintype "passive"))
      (node (ref "J3") (pin "10") (pinfunction "S_10") (pintype "passive"))
      (node (ref "J3") (pin "5") (pinfunction "5_5") (pintype "passive"))
      (node (ref "J3") (pin "9") (pinfunction "S_9") (pintype "passive"))
      (node (ref "J4") (pin "2") (pinfunction "2_2") (pintype "passive"))
      (node (ref "J5") (pin "3") (pinfunction "3_3") (pintype "passive"))
      (node (ref "J6") (pin "4") (pinfunction "ID_4") (pintype "passive"))
      (node (ref "J6") (pin "5") (pinfunction "GND_5") (pintype "passive"))
      (node (ref "J6") (pin "6") (pinfunction "SH1_6") (pintype "passive"))
      (node (ref "J6") (pin "7") (pinfunction "SH2_7") (pintype "passive"))
      (node (ref "J6") (pin "8") (pinfunction "SH3_8") (pintype "passive"))
      (node (ref "J6") (pin "9") (pinfunction "SH4_9") (pintype "passive"))
      (node (ref "L22") (pin "1") (pinfunction "1_1") (pintype "passive"))
      (node (ref "R14") (pin "2") (pinfunction "2_2") (pintype "passive"))
      (node (ref "R57") (pin "1") (pinfunction "1_1") (pintype "passive"))
      (node (ref "U1") (pin "1") (pinfunction "GND_1") (pintype "passive"))
      (node (ref "U10") (pin "4") (pinfunction "GND_4") (pintype "passive"))
      (node (ref "U11") (pin "2") (pinfunction "GND_2") (pintype "passive"))
      (node (ref "U12") (pin "5") (pinfunction "Vss_5") (pintype "passive"))
      (node (ref "U13") (pin "5") (pinfunction "Vss_5") (pintype "passive"))
      (node (ref "U14") (pin "5") (pinfunction "Vss_5") (pintype "passive"))
      (node (ref "U15") (pin "5") (pinfunction "Vss_5") (pintype "passive"))
      (node (ref "U16") (pin "2") (pinfunction "-VS_2") (pintype "passive"))
      (node (ref "U17") (pin "10") (pinfunction "VSS_10") (pintype "power_in"))
      (node (ref "U17") (pin "27") (pinfunction "VSS_27") (pintype "power_in"))
      (node (ref "U17") (pin "49") (pinfunction "VSS_49") (pintype "power_in"))
      (node (ref "U17") (pin "74") (pinfunction "VSS_74") (pintype "power_in"))
      (node (ref "U17") (pin "94") (pinfunction "BOOT0_94") (pintype "input"))
      (node (ref "U17") (pin "99") (pinfunction "VSS_99") (pintype "power_in"))
      (node (ref "U19") (pin "2") (pinfunction "GND_2") (pintype "passive"))
      (node (ref "U19") (pin "8") (pinfunction "STB_8") (pintype "passive"))
      (node (ref "U19") (pin "9") (pinfunction "EP_9") (pintype "passive"))
      (node (ref "U2") (pin "2") (pinfunction "-VS_2") (pintype "passive"))
      (node (ref "U3") (pin "2") (pinfunction "-VS_2") (pintype "passive"))
      (node (ref "U4") (pin "2") (pinfunction "-VS_2") (pintype "passive"))
      (node (ref "U5") (pin "2") (pinfunction "-VS_2") (pintype "passive"))
      (node (ref "U6") (pin "5") (pinfunction "Vss_5") (pintype "passive"))
      (node (ref "U7") (pin "5") (pinfunction "Vss_5") (pintype "passive"))
      (node (ref "U8") (pin "5") (pinfunction "Vss_5") (pintype "passive"))
      (node (ref "U9") (pin "5") (pinfunction "Vss_5") (pintype "passive"))
    )
    (net (code "24") (name "Net-(C4-Pad2)") (class "Default")
      (node (ref "C4") (pin "2") (pinfunction "2_2") (pintype "passive"))
      (node (ref "J4") (pin "1") (pinfunction "1_1") (pintype "passive"))
      (node (ref "L1") (pin "2") (pinfunction "2_2") (pintype "passive"))
    )
    (net (code "25") (name "Net-(C6-Pad2)") (class "Default")
      (node (ref "C6") (pin "2") (pinfunction "2_2") (pintype "passive"))
      (node (ref "R12") (pin "2") (pinfunction "2_2") (pintype "passive"))
      (node (ref "R13") (pin "1") (pinfunction "1_1") (pintype "passive"))
    )
    (net (code "26") (name "Net-(C7-Pad2)") (class "Default")
      (node (ref "C7") (pin "2") (pinfunction "2_2") (pintype "passive"))
      (node (ref "R15") (pin "2") (pinfunction "2_2") (pintype "passive"))
      (node (ref "R4") (pin "2") (pinfunction "2_2") (pintype "passive"))
      (node (ref "R8") (pin "2") (pinfunction "2_2") (pintype "passive"))
      (node (ref "T1") (pin "4") (pinfunction "4_4") (pintype "passive"))
    )
    (net (code "27") (name "Net-(C8-Pad2)") (class "Default")
      (node (ref "C8") (pin "2") (pinfunction "2_2") (pintype "passive"))
      (node (ref "R16") (pin "2") (pinfunction "2_2") (pintype "passive"))
      (node (ref "R5") (pin "2") (pinfunction "2_2") (pintype "passive"))
      (node (ref "R9") (pin "2") (pinfunction "2_2") (pintype "passive"))
      (node (ref "T2") (pin "4") (pinfunction "4_4") (pintype "passive"))
    )
    (net (code "28") (name "Net-(C9-Pad2)") (class "Default")
      (node (ref "C9") (pin "2") (pinfunction "2_2") (pintype "passive"))
      (node (ref "R10") (pin "2") (pinfunction "2_2") (pintype "passive"))
      (node (ref "R17") (pin "2") (pinfunction "2_2") (pintype "passive"))
      (node (ref "R6") (pin "2") (pinfunction "2_2") (pintype "passive"))
      (node (ref "T3") (pin "4") (pinfunction "4_4") (pintype "passive"))
    )
    (net (code "29") (name "Net-(C10-Pad2)") (class "Default")
      (node (ref "C10") (pin "2") (pinfunction "2_2") (pintype "passive"))
      (node (ref "C4") (pin "1") (pinfunction "1_1") (pintype "passive"))
      (node (ref "R11") (pin "2") (pinfunction "2_2") (pintype "passive"))
      (node (ref "R18") (pin "2") (pinfunction "2_2") (pintype "passive"))
      (node (ref "R7") (pin "2") (pinfunction "2_2") (pintype "passive"))
    )
    (net (code "30") (name "Net-(C12-Pad2)") (class "Default")
      (node (ref "C12") (pin "2") (pinfunction "2_2") (pintype "passive"))
      (node (ref "L3") (pin "1") (pinfunction "1_1") (pintype "passive"))
      (node (ref "R15") (pin "1") (pinfunction "1_1") (pintype "passive"))
    )
    (net (code "31") (name "Net-(C13-Pad2)") (class "Default")
      (node (ref "C13") (pin "2") (pinfunction "2_2") (pintype "passive"))
      (node (ref "L4") (pin "1") (pinfunction "1_1") (pintype "passive"))
      (node (ref "R16") (pin "1") (pinfunction "1_1") (pintype "passive"))
    )
    (net (code "32") (name "Net-(C14-Pad2)") (class "Default")
      (node (ref "C14") (pin "2") (pinfunction "2_2") (pintype "passive"))
      (node (ref "L5") (pin "1") (pinfunction "1_1") (pintype "passive"))
      (node (ref "R17") (pin "1") (pinfunction "1_1") (pintype "passive"))
    )
    (net (code "33") (name "Net-(C15-Pad2)") (class "Default")
      (node (ref "C15") (pin "2") (pinfunction "2_2") (pintype "passive"))
      (node (ref "L6") (pin "1") (pinfunction "1_1") (pintype "passive"))
      (node (ref "R18") (pin "1") (pinfunction "1_1") (pintype "passive"))
    )
    (net (code "34") (name "Net-(C17-Pad2)") (class "Default")
      (node (ref "C17") (pin "2") (pinfunction "2_2") (pintype "passive"))
      (node (ref "L3") (pin "2") (pinfunction "2_2") (pintype "passive"))
      (node (ref "L7") (pin "1") (pinfunction "1_1") (pintype "passive"))
    )
    (net (code "35") (name "Net-(C18-Pad2)") (class "Default")
      (node (ref "C18") (pin "2") (pinfunction "2_2") (pintype "passive"))
      (node (ref "L4") (pin "2") (pinfunction "2_2") (pintype "passive"))
      (node (ref "L8") (pin "1") (pinfunction "1_1") (pintype "passive"))
    )
    (net (code "36") (name "Net-(C19-Pad2)") (class "Default")
      (node (ref "C19") (pin "2") (pinfunction "2_2") (pintype "passive"))
      (node (ref "L5") (pin "2") (pinfunction "2_2") (pintype "passive"))
      (node (ref "L9") (pin "1") (pinfunction "1_1") (pintype "passive"))
    )
    (net (code "37") (name "Net-(C20-Pad2)") (class "Default")
      (node (ref "C20") (pin "2") (pinfunction "2_2") (pintype "passive"))
      (node (ref "L10") (pin "1") (pinfunction "1_1") (pintype "passive"))
      (node (ref "L6") (pin "2") (pinfunction "2_2") (pintype "passive"))
    )
    (net (code "38") (name "Net-(C21-Pad2)") (class "Default")
      (node (ref "C21") (pin "2") (pinfunction "2_2") (pintype "passive"))
      (node (ref "L11") (pin "1") (pinfunction "1_1") (pintype "passive"))
      (node (ref "L7") (pin "2") (pinfunction "2_2") (pintype "passive"))
    )
    (net (code "39") (name "Net-(C22-Pad2)") (class "Default")
      (node (ref "C22") (pin "2") (pinfunction "2_2") (pintype "passive"))
      (node (ref "L12") (pin "1") (pinfunction "1_1") (pintype "passive"))
      (node (ref "L8") (pin "2") (pinfunction "2_2") (pintype "passive"))
    )
    (net (code "40") (name "Net-(C23-Pad2)") (class "Default")
      (node (ref "C23") (pin "2") (pinfunction "2_2") (pintype "passive"))
      (node (ref "L13") (pin "1") (pinfunction "1_1") (pintype "passive"))
      (node (ref "L9") (pin "2") (pinfunction "2_2") (pintype "passive"))
    )
    (net (code "41") (name "Net-(C24-Pad2)") (class "Default")
      (node (ref "C24") (pin "2") (pinfunction "2_2") (pintype "passive"))
      (node (ref "L10") (pin "2") (pinfunction "2_2") (pintype "passive"))
      (node (ref "L14") (pin "1") (pinfunction "1_1") (pintype "passive"))
    )
    (net (code "42") (name "Net-(C25-Pad2)") (class "Default")
      (node (ref "C25") (pin "2") (pinfunction "2_2") (pintype "passive"))
      (node (ref "C29") (pin "2") (pinfunction "2_2") (pintype "passive"))
      (node (ref "C30") (pin "2") (pinfunction "2_2") (pintype "passive"))
      (node (ref "L11") (pin "2") (pinfunction "2_2") (pintype "passive"))
      (node (ref "R19") (pin "2") (pinfunction "2_2") (pintype "passive"))
    )
    (net (code "43") (name "Net-(C26-Pad2)") (class "Default")
      (node (ref "C26") (pin "2") (pinfunction "2_2") (pintype "passive"))
      (node (ref "C31") (pin "2") (pinfunction "2_2") (pintype "passive"))
      (node (ref "C32") (pin "2") (pinfunction "2_2") (pintype "passive"))
      (node (ref "L12") (pin "2") (pinfunction "2_2") (pintype "passive"))
      (node (ref "R20") (pin "2") (pinfunction "2_2") (pintype "passive"))
    )
    (net (code "44") (name "Net-(C27-Pad2)") (class "Default")
      (node (ref "C27") (pin "2") (pinfunction "2_2") (pintype "passive"))
      (node (ref "C33") (pin "2") (pinfunction "2_2") (pintype "passive"))
      (node (ref "C34") (pin "2") (pinfunction "2_2") (pintype "passive"))
      (node (ref "L13") (pin "2") (pinfunction "2_2") (pintype "passive"))
      (node (ref "R21") (pin "2") (pinfunction "2_2") (pintype "passive"))
    )
    (net (code "45") (name "Net-(C28-Pad2)") (class "Default")
      (node (ref "C28") (pin "2") (pinfunction "2_2") (pintype "passive"))
      (node (ref "C35") (pin "2") (pinfunction "2_2") (pintype "passive"))
      (node (ref "C36") (pin "2") (pinfunction "2_2") (pintype "passive"))
      (node (ref "L14") (pin "2") (pinfunction "2_2") (pintype "passive"))
      (node (ref "R22") (pin "2") (pinfunction "2_2") (pintype "passive"))
    )
    (net (code "46") (name "Net-(C30-Pad1)") (class "Default")
      (node (ref "C30") (pin "1") (pinfunction "1_1") (pintype "passive"))
      (node (ref "C37") (pin "2") (pinfunction "2_2") (pintype "passive"))
      (node (ref "R26") (pin "2") (pinfunction "2_2") (pintype "passive"))
    )
    (net (code "47") (name "Net-(C32-Pad1)") (class "Default")
      (node (ref "C32") (pin "1") (pinfunction "1_1") (pintype "passive"))
      (node (ref "C38") (pin "2") (pinfunction "2_2") (pintype "passive"))
      (node (ref "R27") (pin "2") (pinfunction "2_2") (pintype "passive"))
    )
    (net (code "48") (name "Net-(C34-Pad1)") (class "Default")
      (node (ref "C34") (pin "1") (pinfunction "1_1") (pintype "passive"))
      (node (ref "C39") (pin "2") (pinfunction "2_2") (pintype "passive"))
      (node (ref "R28") (pin "2") (pinfunction "2_2") (pintype "passive"))
    )
    (net (code "49") (name "Net-(C36-Pad1)") (class "Default")
      (node (ref "C36") (pin "1") (pinfunction "1_1") (pintype "passive"))
      (node (ref "C43") (pin "2") (pinfunction "2_2") (pintype "passive"))
      (node (ref "R32") (pin "2") (pinfunction "2_2") (pintype "passive"))
    )
    (net (code "50") (name "Net-(C37-Pad1)") (class "Default")
      (node (ref "C37") (pin "1") (pinfunction "1_1") (pintype "passive"))
      (node (ref "C40") (pin "2") (pinfunction "2_2") (pintype "passive"))
      (node (ref "R29") (pin "2") (pinfunction "2_2") (pintype "passive"))
    )
    (net (code "51") (name "Net-(C38-Pad1)") (class "Default")
      (node (ref "C38") (pin "1") (pinfunction "1_1") (pintype "passive"))
      (node (ref "C41") (pin "2") (pinfunction "2_2") (pintype "passive"))
      (node (ref "R30") (pin "2") (pinfunction "2_2") (pintype "passive"))
    )
    (net (code "52") (name "Net-(C39-Pad1)") (class "Default")
      (node (ref "C39") (pin "1") (pinfunction "1_1") (pintype "passive"))
      (node (ref "C42") (pin "2") (pinfunction "2_2") (pintype "passive"))
      (node (ref "R31") (pin "2") (pinfunction "2_2") (pintype "passive"))
    )
    (net (code "53") (name "Net-(C81-Pad1)") (class "Default")
      (node (ref "C81") (pin "1") (pinfunction "1_1") (pintype "passive"))
      (node (ref "L17") (pin "1") (pinfunction "1_1") (pintype "passive"))
      (node (ref "R52") (pin "1") (pinfunction "1_1") (pintype "passive"))
    )
    (net (code "54") (name "Net-(C82-Pad1)") (class "Default")
      (node (ref "C82") (pin "1") (pinfunction "1_1") (pintype "passive"))
      (node (ref "L18") (pin "1") (pinfunction "1_1") (pintype "passive"))
      (node (ref "R53") (pin "1") (pinfunction "1_1") (pintype "passive"))
    )
    (net (code "55") (name "Net-(C83-Pad1)") (class "Default")
      (node (ref "C83") (pin "1") (pinfunction "1_1") (pintype "passive"))
      (node (ref "L19") (pin "1") (pinfunction "1_1") (pintype "passive"))
      (node (ref "R54") (pin "1") (pinfunction "1_1") (pintype "passive"))
    )
    (net (code "56") (name "Net-(C84-Pad1)") (class "Default")
      (node (ref "C84") (pin "1") (pinfunction "1_1") (pintype "passive"))
      (node (ref "L20") (pin "1") (pinfunction "1_1") (pintype "passive"))
      (node (ref "R55") (pin "1") (pinfunction "1_1") (pintype "passive"))
    )
    (net (code "57") (name "Net-(J3-Pad1)") (class "Default")
      (node (ref "J3") (pin "1") (pinfunction "1_1") (pintype "passive"))
      (node (ref "R1") (pin "2") (pinfunction "2_2") (pintype "passive"))
      (node (ref "T1") (pin "1") (pinfunction "1_1") (pintype "passive"))
    )
    (net (code "58") (name "Net-(J3-Pad2)") (class "Default")
      (node (ref "J3") (pin "2") (pinfunction "2_2") (pintype "passive"))
      (node (ref "R1") (pin "1") (pinfunction "1_1") (pintype "passive"))
      (node (ref "T1") (pin "3") (pinfunction "3_3") (pintype "passive"))
    )
    (net (code "59") (name "Net-(J3-Pad3)") (class "Default")
      (node (ref "J3") (pin "3") (pinfunction "3_3") (pintype "passive"))
      (node (ref "R2") (pin "2") (pinfunction "2_2") (pintype "passive"))
      (node (ref "T2") (pin "1") (pinfunction "1_1") (pintype "passive"))
    )
    (net (code "60") (name "Net-(J3-Pad6)") (class "Default")
      (node (ref "J3") (pin "6") (pinfunction "6_6") (pintype "passive"))
      (node (ref "R2") (pin "1") (pinfunction "1_1") (pintype "passive"))
      (node (ref "T2") (pin "3") (pinfunction "3_3") (pintype "passive"))
    )
    (net (code "61") (name "Net-(J3-Pad7)") (class "Default")
      (node (ref "J3") (pin "7") (pinfunction "7_7") (pintype "passive"))
      (node (ref "R3") (pin "2") (pinfunction "2_2") (pintype "passive"))
      (node (ref "T3") (pin "1") (pinfunction "1_1") (pintype "passive"))
    )
    (net (code "62") (name "Net-(J3-Pad8)") (class "Default")
      (node (ref "J3") (pin "8") (pinfunction "8_8") (pintype "passive"))
      (node (ref "R3") (pin "1") (pinfunction "1_1") (pintype "passive"))
      (node (ref "T3") (pin "3") (pinfunction "3_3") (pintype "passive"))
    )
    (net (code "63") (name "Net-(U1-BOOT)") (class "Default")
      (node (ref "C5") (pin "1") (pinfunction "1_1") (pintype "passive"))
      (node (ref "U1") (pin "6") (pinfunction "BOOT_6") (pintype "passive"))
    )
    (net (code "64") (name "Net-(U1-FB)") (class "Default")
      (node (ref "C6") (pin "1") (pinfunction "1_1") (pintype "passive"))
      (node (ref "R13") (pin "2") (pinfunction "2_2") (pintype "passive"))
      (node (ref "R14") (pin "1") (pinfunction "1_1") (pintype "passive"))
      (node (ref "U1") (pin "4") (pinfunction "FB_4") (pintype "passive"))
    )
    (net (code "65") (name "Net-(U1-SW)") (class "Default")
      (node (ref "C5") (pin "2") (pinfunction "2_2") (pintype "passive"))
      (node (ref "L2") (pin "1") (pinfunction "1_1") (pintype "passive"))
      (node (ref "U1") (pin "2") (pinfunction "SW_2") (pintype "passive"))
    )
    (net (code "66") (name "Net-(U2-+IN)") (class "Default")
      (node (ref "C40") (pin "1") (pinfunction "1_1") (pintype "passive"))
      (node (ref "R34") (pin "2") (pinfunction "2_2") (pintype "passive"))
      (node (ref "U2") (pin "3") (pinfunction "+IN_3") (pintype "passive"))
    )
    (net (code "67") (name "Net-(U2--IN)") (class "Default")
      (node (ref "R23") (pin "1") (pinfunction "1_1") (pintype "passive"))
      (node (ref "R33") (pin "2") (pinfunction "2_2") (pintype "passive"))
      (node (ref "U2") (pin "4") (pinfunction "-IN_4") (pintype "passive"))
    )
    (net (code "68") (name "Net-(U2-OUT)") (class "Default")
      (node (ref "C48") (pin "2") (pinfunction "2_2") (pintype "passive"))
      (node (ref "R29") (pin "1") (pinfunction "1_1") (pintype "passive"))
      (node (ref "R33") (pin "1") (pinfunction "1_1") (pintype "passive"))
      (node (ref "U2") (pin "1") (pinfunction "OUT_1") (pintype "passive"))
    )
    (net (code "69") (name "Net-(U3-+IN)") (class "Default")
      (node (ref "C41") (pin "1") (pinfunction "1_1") (pintype "passive"))
      (node (ref "R36") (pin "2") (pinfunction "2_2") (pintype "passive"))
      (node (ref "U3") (pin "3") (pinfunction "+IN_3") (pintype "passive"))
    )
    (net (code "70") (name "Net-(U3--IN)") (class "Default")
      (node (ref "R24") (pin "1") (pinfunction "1_1") (pintype "passive"))
      (node (ref "R35") (pin "2") (pinfunction "2_2") (pintype "passive"))
      (node (ref "U3") (pin "4") (pinfunction "-IN_4") (pintype "passive"))
    )
    (net (code "71") (name "Net-(U3-OUT)") (class "Default")
      (node (ref "C49") (pin "2") (pinfunction "2_2") (pintype "passive"))
      (node (ref "R30") (pin "1") (pinfunction "1_1") (pintype "passive"))
      (node (ref "R35") (pin "1") (pinfunction "1_1") (pintype "passive"))
      (node (ref "U3") (pin "1") (pinfunction "OUT_1") (pintype "passive"))
    )
    (net (code "72") (name "Net-(U4-+IN)") (class "Default")
      (node (ref "C42") (pin "1") (pinfunction "1_1") (pintype "passive"))
      (node (ref "R38") (pin "2") (pinfunction "2_2") (pintype "passive"))
      (node (ref "U4") (pin "3") (pinfunction "+IN_3") (pintype "passive"))
    )
    (net (code "73") (name "Net-(U4--IN)") (class "Default")
      (node (ref "R25") (pin "1") (pinfunction "1_1") (pintype "passive"))
      (node (ref "R37") (pin "2") (pinfunction "2_2") (pintype "passive"))
      (node (ref "U4") (pin "4") (pinfunction "-IN_4") (pintype "passive"))
    )
    (net (code "74") (name "Net-(U4-OUT)") (class "Default")
      (node (ref "C50") (pin "2") (pinfunction "2_2") (pintype "passive"))
      (node (ref "R31") (pin "1") (pinfunction "1_1") (pintype "passive"))
      (node (ref "R37") (pin "1") (pinfunction "1_1") (pintype "passive"))
      (node (ref "U4") (pin "1") (pinfunction "OUT_1") (pintype "passive"))
    )
    (net (code "75") (name "Net-(U5-+IN)") (class "Default")
      (node (ref "C43") (pin "1") (pinfunction "1_1") (pintype "passive"))
      (node (ref "R39") (pin "2") (pinfunction "2_2") (pintype "passive"))
      (node (ref "U5") (pin "3") (pinfunction "+IN_3") (pintype "passive"))
    )
    (net (code "76") (name "Net-(U5--IN)") (class "Default")
      (node (ref "C51") (pin "2") (pinfunction "2_2") (pintype "passive"))
      (node (ref "R32") (pin "1") (pinfunction "1_1") (pintype "passive"))
      (node (ref "U5") (pin "1") (pinfunction "OUT_1") (pintype "passive"))
      (node (ref "U5") (pin "4") (pinfunction "-IN_4") (pintype "passive"))
    )
    (net (code "77") (name "Net-(U6-CH0)") (class "Default")
      (node (ref "C48") (pin "1") (pinfunction "1_1") (pintype "passive"))
      (node (ref "R40") (pin "2") (pinfunction "2_2") (pintype "passive"))
      (node (ref "U6") (pin "2") (pinfunction "CH0_2") (pintype "passive"))
    )
    (net (code "78") (name "Net-(U6-CH1)") (class "Default")
      (node (ref "C29") (pin "1") (pinfunction "1_1") (pintype "passive"))
      (node (ref "R44") (pin "2") (pinfunction "2_2") (pintype "passive"))
      (node (ref "U6") (pin "3") (pinfunction "CH1_3") (pintype "passive"))
    )
    (net (code "79") (name "Net-(U6-Vout)") (class "Default")
      (node (ref "C61") (pin "2") (pinfunction "2_2") (pintype "passive"))
      (node (ref "U6") (pin "1") (pinfunction "Vout_1") (pintype "passive"))
    )
    (net (code "80") (name "Net-(U7-CH0)") (class "Default")
      (node (ref "C49") (pin "1") (pinfunction "1_1") (pintype "passive"))
      (node (ref "R41") (pin "2") (pinfunction "2_2") (pintype "passive"))
      (node (ref "U7") (pin "2") (pinfunction "CH0_2") (pintype "passive"))
    )
    (net (code "81") (name "Net-(U7-CH1)") (class "Default")
      (node (ref "C31") (pin "1") (pinfunction "1_1") (pintype "passive"))
      (node (ref "R45") (pin "2") (pinfunction "2_2") (pintype "passive"))
      (node (ref "U7") (pin "3") (pinfunction "CH1_3") (pintype "passive"))
    )
    (net (code "82") (name "Net-(U7-Vout)") (class "Default")
      (node (ref "C62") (pin "2") (pinfunction "2_2") (pintype "passive"))
      (node (ref "U7") (pin "1") (pinfunction "Vout_1") (pintype "passive"))
    )
    (net (code "83") (name "Net-(U8-CH0)") (class "Default")
      (node (ref "C50") (pin "1") (pinfunction "1_1") (pintype "passive"))
      (node (ref "R42") (pin "2") (pinfunction "2_2") (pintype "passive"))
      (node (ref "U8") (pin "2") (pinfunction "CH0_2") (pintype "passive"))
    )
    (net (code "84") (name "Net-(U8-CH1)") (class "Default")
      (node (ref "C33") (pin "1") (pinfunction "1_1") (pintype "passive"))
      (node (ref "R46") (pin "2") (pinfunction "2_2") (pintype "passive"))
      (node (ref "U8") (pin "3") (pinfunction "CH1_3") (pintype "passive"))
    )
    (net (code "85") (name "Net-(U8-Vout)") (class "Default")
      (node (ref "C63") (pin "2") (pinfunction "2_2") (pintype "passive"))
      (node (ref "U8") (pin "1") (pinfunction "Vout_1") (pintype "passive"))
    )
    (net (code "86") (name "Net-(U9-CH0)") (class "Default")
      (node (ref "C51") (pin "1") (pinfunction "1_1") (pintype "passive"))
      (node (ref "R43") (pin "2") (pinfunction "2_2") (pintype "passive"))
      (node (ref "U9") (pin "2") (pinfunction "CH0_2") (pintype "passive"))
    )
    (net (code "87") (name "Net-(U9-CH1)") (class "Default")
      (node (ref "C35") (pin "1") (pinfunction "1_1") (pintype "passive"))
      (node (ref "R47") (pin "2") (pinfunction "2_2") (pintype "passive"))
      (node (ref "U9") (pin "3") (pinfunction "CH1_3") (pintype "passive"))
    )
    (net (code "88") (name "Net-(U9-Vout)") (class "Default")
      (node (ref "C64") (pin "2") (pinfunction "2_2") (pintype "passive"))
      (node (ref "U9") (pin "1") (pinfunction "Vout_1") (pintype "passive"))
    )
    (net (code "89") (name "Net-(U10-BST)") (class "Default")
      (node (ref "C71") (pin "1") (pinfunction "1_1") (pintype "passive"))
      (node (ref "U10") (pin "6") (pinfunction "BST_6") (pintype "passive"))
    )
    (net (code "90") (name "Net-(U10-SW)") (class "Default")
      (node (ref "C71") (pin "2") (pinfunction "2_2") (pintype "passive"))
      (node (ref "L16") (pin "1") (pinfunction "1_1") (pintype "passive"))
      (node (ref "U10") (pin "5") (pinfunction "SW_5") (pintype "passive"))
    )
    (net (code "91") (name "Net-(U11-EN)") (class "Default")
      (node (ref "C65") (pin "2") (pinfunction "2_2") (pintype "passive"))
      (node (ref "C66") (pin "2") (pinfunction "2_2") (pintype "passive"))
      (node (ref "L15") (pin "2") (pinfunction "2_2") (pintype "passive"))
      (node (ref "U11") (pin "1") (pinfunction "IN_1") (pintype "passive"))
      (node (ref "U11") (pin "3") (pinfunction "EN_3") (pintype "passive"))
    )
    (net (code "92") (name "Net-(U12-CH0)") (class "Default")
      (node (ref "TP1") (pin "1") (pinfunction "1_1") (pintype "passive"))
      (node (ref "U12") (pin "2") (pinfunction "CH0_2") (pintype "passive"))
    )
    (net (code "93") (name "Net-(U12-CH1)") (class "Default")
      (node (ref "C61") (pin "1") (pinfunction "1_1") (pintype "passive"))
      (node (ref "R48") (pin "2") (pinfunction "2_2") (pintype "passive"))
      (node (ref "U12") (pin "3") (pinfunction "CH1_3") (pintype "passive"))
    )
    (net (code "94") (name "Net-(U12-SI)") (class "Default")
      (node (ref "U12") (pin "7") (pinfunction "SI_7") (pintype "passive"))
      (node (ref "U6") (pin "8") (pinfunction "SO_8") (pintype "passive"))
    )
    (net (code "95") (name "Net-(U12-Vout)") (class "Default")
      (node (ref "R52") (pin "2") (pinfunction "2_2") (pintype "passive"))
      (node (ref "U12") (pin "1") (pinfunction "Vout_1") (pintype "passive"))
    )
    (net (code "96") (name "Net-(U13-CH0)") (class "Default")
      (node (ref "TP2") (pin "1") (pinfunction "1_1") (pintype "passive"))
      (node (ref "U13") (pin "2") (pinfunction "CH0_2") (pintype "passive"))
    )
    (net (code "97") (name "Net-(U13-CH1)") (class "Default")
      (node (ref "C62") (pin "1") (pinfunction "1_1") (pintype "passive"))
      (node (ref "R49") (pin "2") (pinfunction "2_2") (pintype "passive"))
      (node (ref "U13") (pin "3") (pinfunction "CH1_3") (pintype "passive"))
    )
    (net (code "98") (name "Net-(U13-SI)") (class "Default")
      (node (ref "U13") (pin "7") (pinfunction "SI_7") (pintype "passive"))
      (node (ref "U7") (pin "8") (pinfunction "SO_8") (pintype "passive"))
    )
    (net (code "99") (name "Net-(U13-SO)") (class "Default")
      (node (ref "U13") (pin "8") (pinfunction "SO_8") (pintype "passive"))
      (node (ref "U6") (pin "7") (pinfunction "SI_7") (pintype "passive"))
    )
    (net (code "100") (name "Net-(U13-Vout)") (class "Default")
      (node (ref "R53") (pin "2") (pinfunction "2_2") (pintype "passive"))
      (node (ref "U13") (pin "1") (pinfunction "Vout_1") (pintype "passive"))
    )
    (net (code "101") (name "Net-(U14-CH0)") (class "Default")
      (node (ref "TP3") (pin "1") (pinfunction "1_1") (pintype "passive"))
      (node (ref "U14") (pin "2") (pinfunction "CH0_2") (pintype "passive"))
    )
    (net (code "102") (name "Net-(U14-CH1)") (class "Default")
      (node (ref "C63") (pin "1") (pinfunction "1_1") (pintype "passive"))
      (node (ref "R50") (pin "2") (pinfunction "2_2") (pintype "passive"))
      (node (ref "U14") (pin "3") (pinfunction "CH1_3") (pintype "passive"))
    )
    (net (code "103") (name "Net-(U14-SI)") (class "Default")
      (node (ref "U14") (pin "7") (pinfunction "SI_7") (pintype "passive"))
      (node (ref "U8") (pin "8") (pinfunction "SO_8") (pintype "passive"))
    )
    (net (code "104") (name "Net-(U14-SO)") (class "Default")
      (node (ref "U14") (pin "8") (pinfunction "SO_8") (pintype "passive"))
      (node (ref "U7") (pin "7") (pinfunction "SI_7") (pintype "passive"))
    )
    (net (code "105") (name "Net-(U14-Vout)") (class "Default")
      (node (ref "R54") (pin "2") (pinfunction "2_2") (pintype "passive"))
      (node (ref "U14") (pin "1") (pinfunction "Vout_1") (pintype "passive"))
    )
    (net (code "106") (name "Net-(U15-CH0)") (class "Default")
      (node (ref "TP4") (pin "1") (pinfunction "1_1") (pintype "passive"))
      (node (ref "U15") (pin "2") (pinfunction "CH0_2") (pintype "passive"))
    )
    (net (code "107") (name "Net-(U15-CH1)") (class "Default")
      (node (ref "C64") (pin "1") (pinfunction "1_1") (pintype "passive"))
      (node (ref "R51") (pin "2") (pinfunction "2_2") (pintype "passive"))
      (node (ref "U15") (pin "3") (pinfunction "CH1_3") (pintype "passive"))
    )
    (net (code "108") (name "Net-(U15-SI)") (class "Default")
      (node (ref "U15") (pin "7") (pinfunction "SI_7") (pintype "passive"))
      (node (ref "U9") (pin "8") (pinfunction "SO_8") (pintype "passive"))
    )
    (net (code "109") (name "Net-(U15-SO)") (class "Default")
      (node (ref "U15") (pin "8") (pinfunction "SO_8") (pintype "passive"))
      (node (ref "U8") (pin "7") (pinfunction "SI_7") (pintype "passive"))
    )
    (net (code "110") (name "Net-(U15-Vout)") (class "Default")
      (node (ref "R55") (pin "2") (pinfunction "2_2") (pintype "passive"))
      (node (ref "U15") (pin "1") (pinfunction "Vout_1") (pintype "passive"))
    )
    (net (code "111") (name "Net-(U16-+IN)") (class "Default")
      (node (ref "C80") (pin "1") (pinfunction "1_1") (pintype "passive"))
      (node (ref "R56") (pin "1") (pinfunction "1_1") (pintype "passive"))
      (node (ref "R57") (pin "2") (pinfunction "2_2") (pintype "passive"))
      (node (ref "U16") (pin "3") (pinfunction "+IN_3") (pintype "passive"))
    )
    (net (code "112") (name "Net-(U16-OUT)") (class "Default")
      (node (ref "R58") (pin "2") (pinfunction "2_2") (pintype "passive"))
      (node (ref "U16") (pin "1") (pinfunction "OUT_1") (pintype "passive"))
    )
    (net (code "113") (name "Net-(U17-NRST)") (class "Default")
      (node (ref "C101") (pin "2") (pinfunction "2_2") (pintype "passive"))
      (node (ref "R60") (pin "2") (pinfunction "2_2") (pintype "passive"))
      (node (ref "U17") (pin "14") (pinfunction "NRST_14") (pintype "bidirectional"))
    )
    (net (code "114") (name "Net-(U17-VDDA)") (class "Default")
      (node (ref "C99") (pin "2") (pinfunction "2_2") (pintype "passive"))
      (node (ref "L21") (pin "2") (pinfunction "2_2") (pintype "passive"))
      (node (ref "U17") (pin "22") (pinfunction "VDDA_22") (pintype "power_in"))
    )
    (net (code "115") (name "VDD") (class "Default")
      (node (ref "C44") (pin "2") (pinfunction "2_2") (pintype "passive"))
      (node (ref "C45") (pin "2") (pinfunction "2_2") (pintype "passive"))
      (node (ref "C46") (pin "2") (pinfunction "2_2") (pintype "passive"))
      (node (ref "C47") (pin "2") (pinfunction "2_2") (pintype "passive"))
      (node (ref "C56") (pin "2") (pinfunction "2_2") (pintype "passive"))
      (node (ref "C57") (pin "2") (pinfunction "2_2") (pintype "passive"))
      (node (ref "C58") (pin "2") (pinfunction "2_2") (pintype "passive"))
      (node (ref "C59") (pin "2") (pinfunction "2_2") (pintype "passive"))
      (node (ref "C72") (pin "2") (pinfunction "2_2") (pintype "passive"))
      (node (ref "C73") (pin "2") (pinfunction "2_2") (pintype "passive"))
      (node (ref "C74") (pin "2") (pinfunction "2_2") (pintype "passive"))
      (node (ref "C75") (pin "2") (pinfunction "2_2") (pintype "passive"))
      (node (ref "C77") (pin "2") (pinfunction "2_2") (pintype "passive"))
      (node (ref "C79") (pin "2") (pinfunction "2_2") (pintype "passive"))
      (node (ref "C89") (pin "2") (pinfunction "2_2") (pintype "passive"))
      (node (ref "U11") (pin "5") (pinfunction "OUT_5") (pintype "passive"))
      (node (ref "U12") (pin "10") (pinfunction "Vdd_10") (pintype "passive"))
      (node (ref "U13") (pin "10") (pinfunction "Vdd_10") (pintype "passive"))
      (node (ref "U14") (pin "10") (pinfunction "Vdd_10") (pintype "passive"))
      (node (ref "U15") (pin "10") (pinfunction "Vdd_10") (pintype "passive"))
      (node (ref "U16") (pin "5") (pinfunction "+VS_5") (pintype "passive"))
      (node (ref "U2") (pin "5") (pinfunction "+VS_5") (pintype "passive"))
      (node (ref "U3") (pin "5") (pinfunction "+VS_5") (pintype "passive"))
      (node (ref "U4") (pin "5") (pinfunction "+VS_5") (pintype "passive"))
      (node (ref "U5") (pin "5") (pinfunction "+VS_5") (pintype "passive"))
      (node (ref "U6") (pin "10") (pinfunction "Vdd_10") (pintype "passive"))
      (node (ref "U7") (pin "10") (pinfunction "Vdd_10") (pintype "passive"))
      (node (ref "U8") (pin "10") (pinfunction "Vdd_10") (pintype "passive"))
      (node (ref "U9") (pin "10") (pinfunction "Vdd_10") (pintype "passive"))
    )
    (net (code "116") (name "VGND") (class "Default")
      (node (ref "C12") (pin "1") (pinfunction "1_1") (pintype "passive"))
      (node (ref "C13") (pin "1") (pinfunction "1_1") (pintype "passive"))
      (node (ref "C14") (pin "1") (pinfunction "1_1") (pintype "passive"))
      (node (ref "C15") (pin "1") (pinfunction "1_1") (pintype "passive"))
      (node (ref "C17") (pin "1") (pinfunction "1_1") (pintype "passive"))
      (node (ref "C18") (pin "1") (pinfunction "1_1") (pintype "passive"))
      (node (ref "C19") (pin "1") (pinfunction "1_1") (pintype "passive"))
      (node (ref "C20") (pin "1") (pinfunction "1_1") (pintype "passive"))
      (node (ref "C21") (pin "1") (pinfunction "1_1") (pintype "passive"))
      (node (ref "C22") (pin "1") (pinfunction "1_1") (pintype "passive"))
      (node (ref "C23") (pin "1") (pinfunction "1_1") (pintype "passive"))
      (node (ref "C24") (pin "1") (pinfunction "1_1") (pintype "passive"))
      (node (ref "C25") (pin "1") (pinfunction "1_1") (pintype "passive"))
      (node (ref "C26") (pin "1") (pinfunction "1_1") (pintype "passive"))
      (node (ref "C27") (pin "1") (pinfunction "1_1") (pintype "passive"))
      (node (ref "C28") (pin "1") (pinfunction "1_1") (pintype "passive"))
      (node (ref "C52") (pin "1") (pinfunction "1_1") (pintype "passive"))
      (node (ref "C53") (pin "1") (pinfunction "1_1") (pintype "passive"))
      (node (ref "C54") (pin "1") (pinfunction "1_1") (pintype "passive"))
      (node (ref "C55") (pin "1") (pinfunction "1_1") (pintype "passive"))
      (node (ref "C67") (pin "1") (pinfunction "1_1") (pintype "passive"))
      (node (ref "C68") (pin "1") (pinfunction "1_1") (pintype "passive"))
      (node (ref "C69") (pin "1") (pinfunction "1_1") (pintype "passive"))
      (node (ref "C70") (pin "1") (pinfunction "1_1") (pintype "passive"))
      (node (ref "C81") (pin "2") (pinfunction "2_2") (pintype "passive"))
      (node (ref "C82") (pin "2") (pinfunction "2_2") (pintype "passive"))
      (node (ref "C83") (pin "2") (pinfunction "2_2") (pintype "passive"))
      (node (ref "C84") (pin "2") (pinfunction "2_2") (pintype "passive"))
      (node (ref "R19") (pin "1") (pinfunction "1_1") (pintype "passive"))
      (node (ref "R20") (pin "1") (pinfunction "1_1") (pintype "passive"))
      (node (ref "R21") (pin "1") (pinfunction "1_1") (pintype "passive"))
      (node (ref "R22") (pin "1") (pinfunction "1_1") (pintype "passive"))
      (node (ref "R23") (pin "2") (pinfunction "2_2") (pintype "passive"))
      (node (ref "R24") (pin "2") (pinfunction "2_2") (pintype "passive"))
      (node (ref "R25") (pin "2") (pinfunction "2_2") (pintype "passive"))
      (node (ref "R26") (pin "1") (pinfunction "1_1") (pintype "passive"))
      (node (ref "R27") (pin "1") (pinfunction "1_1") (pintype "passive"))
      (node (ref "R28") (pin "1") (pinfunction "1_1") (pintype "passive"))
      (node (ref "R34") (pin "1") (pinfunction "1_1") (pintype "passive"))
      (node (ref "R36") (pin "1") (pinfunction "1_1") (pintype "passive"))
      (node (ref "R38") (pin "1") (pinfunction "1_1") (pintype "passive"))
      (node (ref "R39") (pin "1") (pinfunction "1_1") (pintype "passive"))
      (node (ref "R4") (pin "1") (pinfunction "1_1") (pintype "passive"))
      (node (ref "R40") (pin "1") (pinfunction "1_1") (pintype "passive"))
      (node (ref "R41") (pin "1") (pinfunction "1_1") (pintype "passive"))
      (node (ref "R42") (pin "1") (pinfunction "1_1") (pintype "passive"))
      (node (ref "R43") (pin "1") (pinfunction "1_1") (pintype "passive"))
      (node (ref "R44") (pin "1") (pinfunction "1_1") (pintype "passive"))
      (node (ref "R45") (pin "1") (pinfunction "1_1") (pintype "passive"))
      (node (ref "R46") (pin "1") (pinfunction "1_1") (pintype "passive"))
      (node (ref "R47") (pin "1") (pinfunction "1_1") (pintype "passive"))
      (node (ref "R48") (pin "1") (pinfunction "1_1") (pintype "passive"))
      (node (ref "R49") (pin "1") (pinfunction "1_1") (pintype "passive"))
      (node (ref "R5") (pin "1") (pinfunction "1_1") (pintype "passive"))
      (node (ref "R50") (pin "1") (pinfunction "1_1") (pintype "passive"))
      (node (ref "R51") (pin "1") (pinfunction "1_1") (pintype "passive"))
      (node (ref "R58") (pin "1") (pinfunction "1_1") (pintype "passive"))
      (node (ref "R6") (pin "1") (pinfunction "1_1") (pintype "passive"))
      (node (ref "R7") (pin "1") (pinfunction "1_1") (pintype "passive"))
      (node (ref "T1") (pin "6") (pinfunction "6_6") (pintype "passive"))
      (node (ref "T2") (pin "6") (pinfunction "6_6") (pintype "passive"))
      (node (ref "T3") (pin "6") (pinfunction "6_6") (pintype "passive"))
      (node (ref "U12") (pin "4") (pinfunction "Vref_4") (pintype "passive"))
      (node (ref "U13") (pin "4") (pinfunction "Vref_4") (pintype "passive"))
      (node (ref "U14") (pin "4") (pinfunction "Vref_4") (pintype "passive"))
      (node (ref "U15") (pin "4") (pinfunction "Vref_4") (pintype "passive"))
      (node (ref "U16") (pin "4") (pinfunction "-IN_4") (pintype "passive"))
      (node (ref "U6") (pin "4") (pinfunction "Vref_4") (pintype "passive"))
      (node (ref "U7") (pin "4") (pinfunction "Vref_4") (pintype "passive"))
      (node (ref "U8") (pin "4") (pinfunction "Vref_4") (pintype "passive"))
      (node (ref "U9") (pin "4") (pinfunction "Vref_4") (pintype "passive"))
    )
    (net (code "117") (name "unconnected-(U1-EN-Pad5)") (class "Default")
      (node (ref "U1") (pin "5") (pinfunction "EN_5") (pintype "passive"))
    )
    (net (code "118") (name "unconnected-(U17-OSC_IN-Pad12)") (class "Default")
      (node (ref "U17") (pin "12") (pinfunction "OSC_IN_12") (pintype "passive"))
    )
    (net (code "119") (name "unconnected-(U17-OSC_OUT-Pad13)") (class "Default")
      (node (ref "U17") (pin "13") (pinfunction "OSC_OUT_13") (pintype "passive"))
    )
    (net (code "120") (name "unconnected-(U17-PA8-Pad67)") (class "Default")
      (node (ref "U17") (pin "67") (pinfunction "PA8_67") (pintype "bidirectional"))
    )
    (net (code "121") (name "unconnected-(U17-PA9-Pad68)") (class "Default")
      (node (ref "U17") (pin "68") (pinfunction "PA9_68") (pintype "bidirectional"))
    )
    (net (code "122") (name "unconnected-(U17-PA10-Pad69)") (class "Default")
      (node (ref "U17") (pin "69") (pinfunction "PA10_69") (pintype "bidirectional"))
    )
    (net (code "123") (name "unconnected-(U17-PA15-Pad77)") (class "Default")
      (node (ref "U17") (pin "77") (pinfunction "PA15_77") (pintype "bidirectional"))
    )
    (net (code "124") (name "unconnected-(U17-PB0-Pad35)") (class "Default")
      (node (ref "U17") (pin "35") (pinfunction "PB0_35") (pintype "bidirectional"))
    )
    (net (code "125") (name "unconnected-(U17-PB1-Pad36)") (class "Default")
      (node (ref "U17") (pin "36") (pinfunction "PB1_36") (pintype "bidirectional"))
    )
    (net (code "126") (name "unconnected-(U17-PB2-Pad37)") (class "Default")
      (node (ref "U17") (pin "37") (pinfunction "PB2_37") (pintype "bidirectional"))
    )
    (net (code "127") (name "unconnected-(U17-PB3-Pad89)") (class "Default")
      (node (ref "U17") (pin "89") (pinfunction "PB3_89") (pintype "bidirectional"))
    )
    (net (code "128") (name "unconnected-(U17-PB4-Pad90)") (class "Default")
      (node (ref "U17") (pin "90") (pinfunction "PB4_90") (pintype "bidirectional"))
    )
    (net (code "129") (name "unconnected-(U17-PB5-Pad91)") (class "Default")
      (node (ref "U17") (pin "91") (pinfunction "PB5_91") (pintype "bidirectional"))
    )
    (net (code "130") (name "unconnected-(U17-PB6-Pad92)") (class "Default")
      (node (ref "U17") (pin "92") (pinfunction "PB6_92") (pintype "bidirectional"))
    )
    (net (code "131") (name "unconnected-(U17-PB7-Pad93)") (class "Default")
      (node (ref "U17") (pin "93") (pinfunction "PB7_93") (pintype "bidirectional"))
    )
    (net (code "132") (name "unconnected-(U17-PB8-Pad95)") (class "Default")
      (node (ref "U17") (pin "95") (pinfunction "PB8_95") (pintype "bidirectional"))
    )
    (net (code "133") (name "unconnected-(U17-PB9-Pad96)") (class "Default")
      (node (ref "U17") (pin "96") (pinfunction "PB9_96") (pintype "bidirectional"))
    )
    (net (code "134") (name "unconnected-(U17-PB10-Pad47)") (class "Default")
      (node (ref "U17") (pin "47") (pinfunction "PB10_47") (pintype "bidirectional"))
    )
    (net (code "135") (name "unconnected-(U17-PB11-Pad48)") (class "Default")
      (node (ref "U17") (pin "48") (pinfunction "PB11_48") (pintype "bidirectional"))
    )
    (net (code "136") (name "unconnected-(U17-PB12-Pad51)") (class "Default")
      (node (ref "U17") (pin "51") (pinfunction "PB12_51") (pintype "bidirectional"))
    )
    (net (code "137") (name "unconnected-(U17-PB13-Pad52)") (class "Default")
      (node (ref "U17") (pin "52") (pinfunction "PB13_52") (pintype "bidirectional"))
    )
    (net (code "138") (name "unconnected-(U17-PB14-Pad53)") (class "Default")
      (node (ref "U17") (pin "53") (pinfunction "PB14_53") (pintype "bidirectional"))
    )
    (net (code "139") (name "unconnected-(U17-PB15-Pad54)") (class "Default")
      (node (ref "U17") (pin "54") (pinfunction "PB15_54") (pintype "bidirectional"))
    )
    (net (code "140") (name "unconnected-(U17-PC0-Pad15)") (class "Default")
      (node (ref "U17") (pin "15") (pinfunction "PC0_15") (pintype "bidirectional"))
    )
    (net (code "141") (name "unconnected-(U17-PC1-Pad16)") (class "Default")
      (node (ref "U17") (pin "16") (pinfunction "PC1_16") (pintype "bidirectional"))
    )
    (net (code "142") (name "unconnected-(U17-PC2-Pad17)") (class "Default")
      (node (ref "U17") (pin "17") (pinfunction "PC2_17") (pintype "bidirectional"))
    )
    (net (code "143") (name "unconnected-(U17-PC3-Pad18)") (class "Default")
      (node (ref "U17") (pin "18") (pinfunction "PC3_18") (pintype "bidirectional"))
    )
    (net (code "144") (name "unconnected-(U17-PC5-Pad34)") (class "Default")
      (node (ref "U17") (pin "34") (pinfunction "PC5_34") (pintype "bidirectional"))
    )
    (net (code "145") (name "unconnected-(U17-PC6-Pad63)") (class "Default")
      (node (ref "U17") (pin "63") (pinfunction "PC6_63") (pintype "bidirectional"))
    )
    (net (code "146") (name "unconnected-(U17-PC7-Pad64)") (class "Default")
      (node (ref "U17") (pin "64") (pinfunction "PC7_64") (pintype "bidirectional"))
    )
    (net (code "147") (name "unconnected-(U17-PC8-Pad65)") (class "Default")
      (node (ref "U17") (pin "65") (pinfunction "PC8_65") (pintype "bidirectional"))
    )
    (net (code "148") (name "unconnected-(U17-PC9-Pad66)") (class "Default")
      (node (ref "U17") (pin "66") (pinfunction "PC9_66") (pintype "bidirectional"))
    )
    (net (code "149") (name "unconnected-(U17-PC10-Pad78)") (class "Default")
      (node (ref "U17") (pin "78") (pinfunction "PC10_78") (pintype "bidirectional"))
    )
    (net (code "150") (name "unconnected-(U17-PC11-Pad79)") (class "Default")
      (node (ref "U17") (pin "79") (pinfunction "PC11_79") (pintype "bidirectional"))
    )
    (net (code "151") (name "unconnected-(U17-PC12-Pad80)") (class "Default")
      (node (ref "U17") (pin "80") (pinfunction "PC12_80") (pintype "bidirectional"))
    )
    (net (code "152") (name "unconnected-(U17-PC13-TAMPER-RTC-Pad7)") (class "Default")
      (node (ref "U17") (pin "7") (pinfunction "PC13-TAMPER-RTC_7") (pintype "bidirectional"))
    )
    (net (code "153") (name "unconnected-(U17-PC14{slash}OSC32_IN-Pad8)") (class "Default")
      (node (ref "U17") (pin "8") (pinfunction "PC14/OSC32_IN_8") (pintype "bidirectional"))
    )
    (net (code "154") (name "unconnected-(U17-PC15-OSC32_OUT-Pad9)") (class "Default")
      (node (ref "U17") (pin "9") (pinfunction "PC15-OSC32_OUT_9") (pintype "bidirectional"))
    )
    (net (code "155") (name "unconnected-(U17-PD2-Pad83)") (class "Default")
      (node (ref "U17") (pin "83") (pinfunction "PD2_83") (pintype "bidirectional"))
    )
    (net (code "156") (name "unconnected-(U17-PD3-Pad84)") (class "Default")
      (node (ref "U17") (pin "84") (pinfunction "PD3_84") (pintype "bidirectional"))
    )
    (net (code "157") (name "unconnected-(U17-PD4-Pad85)") (class "Default")
      (node (ref "U17") (pin "85") (pinfunction "PD4_85") (pintype "bidirectional"))
    )
    (net (code "158") (name "unconnected-(U17-PD5-Pad86)") (class "Default")
      (node (ref "U17") (pin "86") (pinfunction "PD5_86") (pintype "bidirectional"))
    )
    (net (code "159") (name "unconnected-(U17-PD6-Pad87)") (class "Default")
      (node (ref "U17") (pin "87") (pinfunction "PD6_87") (pintype "bidirectional"))
    )
    (net (code "160") (name "unconnected-(U17-PD7-Pad88)") (class "Default")
      (node (ref "U17") (pin "88") (pinfunction "PD7_88") (pintype "bidirectional"))
    )
    (net (code "161") (name "unconnected-(U17-PD8-Pad55)") (class "Default")
      (node (ref "U17") (pin "55") (pinfunction "PD8_55") (pintype "bidirectional"))
    )
    (net (code "162") (name "unconnected-(U17-PD9-Pad56)") (class "Default")
      (node (ref "U17") (pin "56") (pinfunction "PD9_56") (pintype "bidirectional"))
    )
    (net (code "163") (name "unconnected-(U17-PD10-Pad57)") (class "Default")
      (node (ref "U17") (pin "57") (pinfunction "PD10_57") (pintype "bidirectional"))
    )
    (net (code "164") (name "unconnected-(U17-PD11-Pad58)") (class "Default")
      (node (ref "U17") (pin "58") (pinfunction "PD11_58") (pintype "bidirectional"))
    )
    (net (code "165") (name "unconnected-(U17-PD12-Pad59)") (class "Default")
      (node (ref "U17") (pin "59") (pinfunction "PD12_59") (pintype "bidirectional"))
    )
    (net (code "166") (name "unconnected-(U17-PD13-Pad60)") (class "Default")
      (node (ref "U17") (pin "60") (pinfunction "PD13_60") (pintype "bidirectional"))
    )
    (net (code "167") (name "unconnected-(U17-PD14-Pad61)") (class "Default")
      (node (ref "U17") (pin "61") (pinfunction "PD14_61") (pintype "bidirectional"))
    )
    (net (code "168") (name "unconnected-(U17-PD15-Pad62)") (class "Default")
      (node (ref "U17") (pin "62") (pinfunction "PD15_62") (pintype "bidirectional"))
    )
    (net (code "169") (name "unconnected-(U17-PE0-Pad97)") (class "Default")
      (node (ref "U17") (pin "97") (pinfunction "PE0_97") (pintype "bidirectional"))
    )
    (net (code "170") (name "unconnected-(U17-PE1-Pad98)") (class "Default")
      (node (ref "U17") (pin "98") (pinfunction "PE1_98") (pintype "bidirectional"))
    )
    (net (code "171") (name "unconnected-(U17-PE2-Pad1)") (class "Default")
      (node (ref "U17") (pin "1") (pinfunction "PE2_1") (pintype "bidirectional"))
    )
    (net (code "172") (name "unconnected-(U17-PE3-Pad2)") (class "Default")
      (node (ref "U17") (pin "2") (pinfunction "PE3_2") (pintype "bidirectional"))
    )
    (net (code "173") (name "unconnected-(U17-PE4-Pad3)") (class "Default")
      (node (ref "U17") (pin "3") (pinfunction "PE4_3") (pintype "bidirectional"))
    )
    (net (code "174") (name "unconnected-(U17-PE5-Pad4)") (class "Default")
      (node (ref "U17") (pin "4") (pinfunction "PE5_4") (pintype "bidirectional"))
    )
    (net (code "175") (name "unconnected-(U17-PE6-Pad5)") (class "Default")
      (node (ref "U17") (pin "5") (pinfunction "PE6_5") (pintype "bidirectional"))
    )
    (net (code "176") (name "unconnected-(U17-PE7-Pad38)") (class "Default")
      (node (ref "U17") (pin "38") (pinfunction "PE7_38") (pintype "bidirectional"))
    )
    (net (code "177") (name "unconnected-(U17-PE8-Pad39)") (class "Default")
      (node (ref "U17") (pin "39") (pinfunction "PE8_39") (pintype "bidirectional"))
    )
    (net (code "178") (name "unconnected-(U17-PE9-Pad40)") (class "Default")
      (node (ref "U17") (pin "40") (pinfunction "PE9_40") (pintype "bidirectional"))
    )
    (net (code "179") (name "unconnected-(U17-PE10-Pad41)") (class "Default")
      (node (ref "U17") (pin "41") (pinfunction "PE10_41") (pintype "bidirectional"))
    )
    (net (code "180") (name "unconnected-(U17-PE11-Pad42)") (class "Default")
      (node (ref "U17") (pin "42") (pinfunction "PE11_42") (pintype "bidirectional"))
    )
    (net (code "181") (name "unconnected-(U17-PE12-Pad43)") (class "Default")
      (node (ref "U17") (pin "43") (pinfunction "PE12_43") (pintype "bidirectional"))
    )
    (net (code "182") (name "unconnected-(U17-PE13-Pad44)") (class "Default")
      (node (ref "U17") (pin "44") (pinfunction "PE13_44") (pintype "bidirectional"))
    )
    (net (code "183") (name "unconnected-(U17-PE14-Pad45)") (class "Default")
      (node (ref "U17") (pin "45") (pinfunction "PE14_45") (pintype "bidirectional"))
    )
    (net (code "184") (name "unconnected-(U17-PE15-Pad46)") (class "Default")
      (node (ref "U17") (pin "46") (pinfunction "PE15_46") (pintype "bidirectional"))
    )
  )
)
